# 8iPanelLED.net
KiCad netlist of a schematic drawn in EAGLE
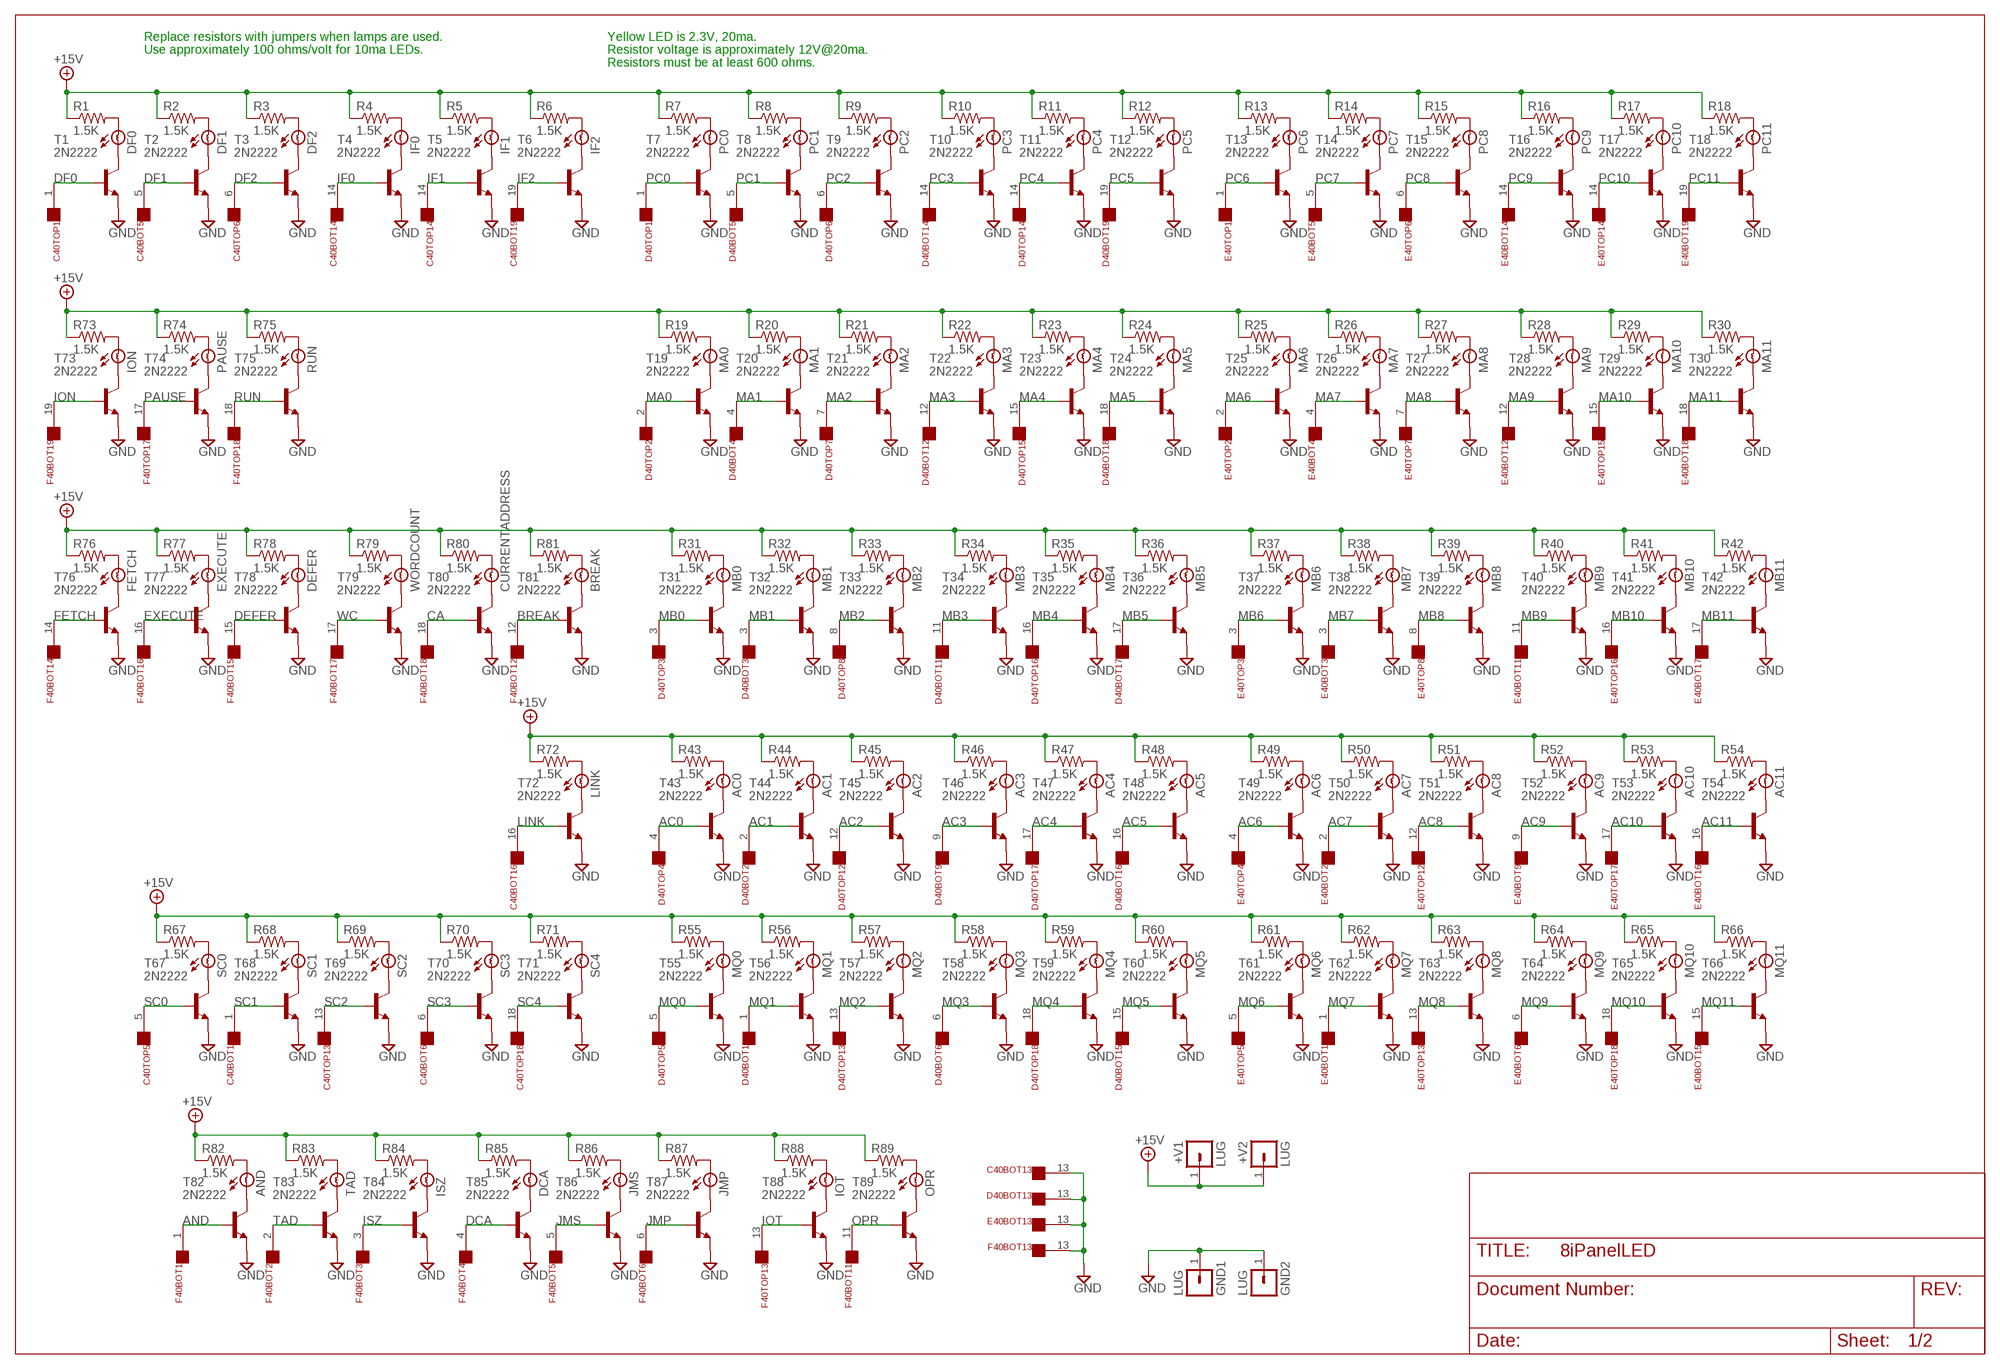
[diagram p0: schematic, sheet 1]
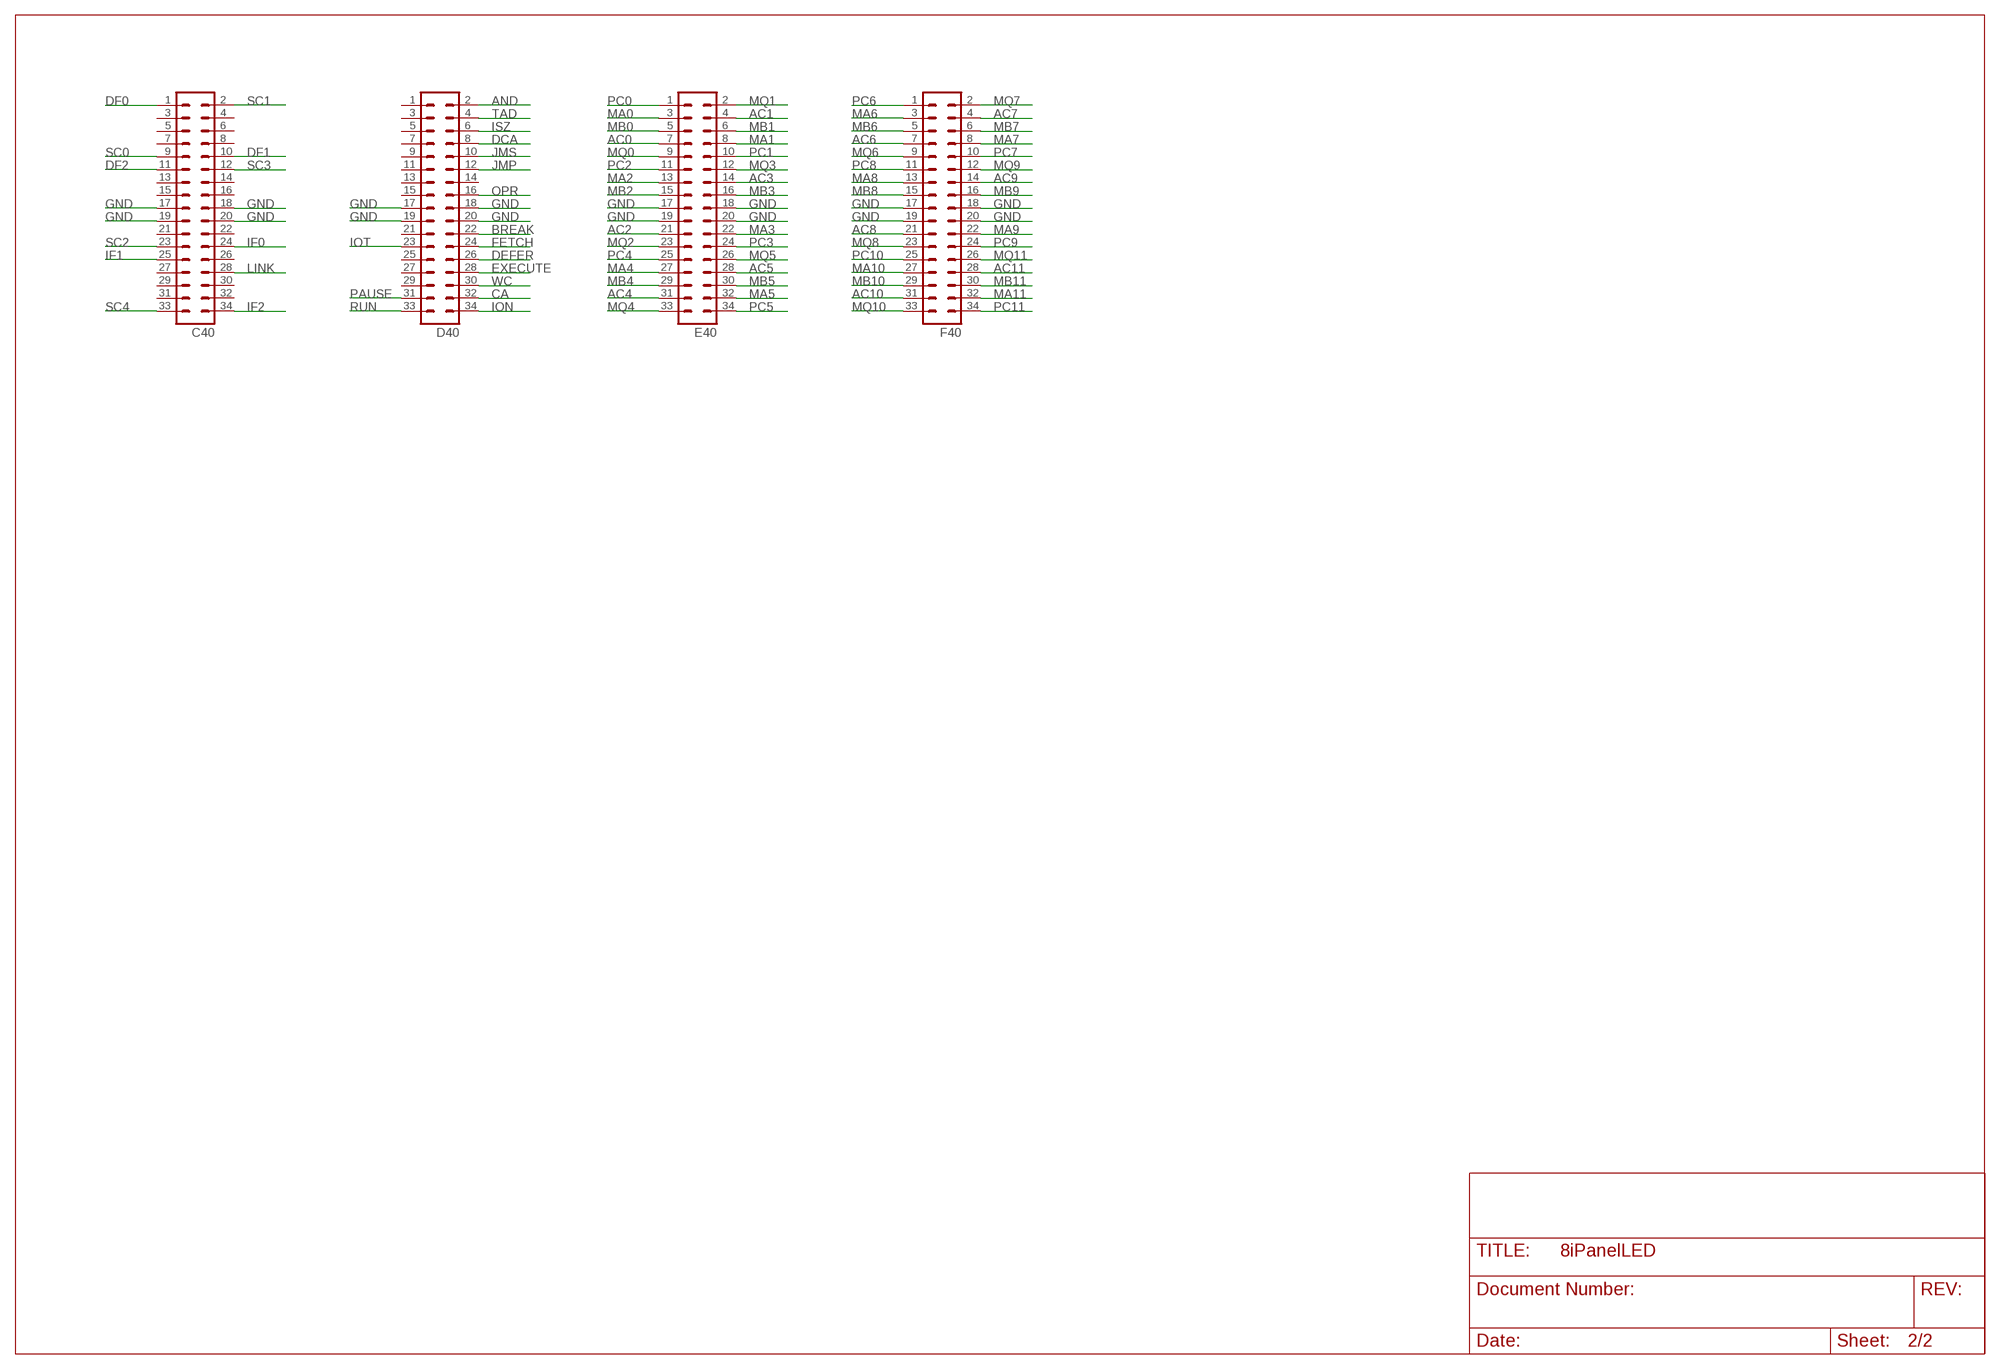
[diagram p1: schematic, sheet 2]

(export (version "E")
  (design (tool "Eeschema 10.0.6"))
  (components
    (comp (ref "+V1")
      (value "LUG")
      (footprint "eagle-import:SPADELUG")
      (libsource (lib "eagle-import") (part "LUG"))
    )
    (comp (ref "+V2")
      (value "LUG")
      (footprint "eagle-import:SPADELUG")
      (libsource (lib "eagle-import") (part "LUG"))
    )
    (comp (ref "AC0")
      (value "BULB")
      (footprint "eagle-import:BULB")
      (libsource (lib "eagle-import") (part "BULB"))
    )
    (comp (ref "AC1")
      (value "BULB")
      (footprint "eagle-import:BULB")
      (libsource (lib "eagle-import") (part "BULB"))
    )
    (comp (ref "AC2")
      (value "BULB")
      (footprint "eagle-import:BULB")
      (libsource (lib "eagle-import") (part "BULB"))
    )
    (comp (ref "AC3")
      (value "BULB")
      (footprint "eagle-import:BULB")
      (libsource (lib "eagle-import") (part "BULB"))
    )
    (comp (ref "AC4")
      (value "BULB")
      (footprint "eagle-import:BULB")
      (libsource (lib "eagle-import") (part "BULB"))
    )
    (comp (ref "AC5")
      (value "BULB")
      (footprint "eagle-import:BULB")
      (libsource (lib "eagle-import") (part "BULB"))
    )
    (comp (ref "AC6")
      (value "BULB")
      (footprint "eagle-import:BULB")
      (libsource (lib "eagle-import") (part "BULB"))
    )
    (comp (ref "AC7")
      (value "BULB")
      (footprint "eagle-import:BULB")
      (libsource (lib "eagle-import") (part "BULB"))
    )
    (comp (ref "AC8")
      (value "BULB")
      (footprint "eagle-import:BULB")
      (libsource (lib "eagle-import") (part "BULB"))
    )
    (comp (ref "AC9")
      (value "BULB")
      (footprint "eagle-import:BULB")
      (libsource (lib "eagle-import") (part "BULB"))
    )
    (comp (ref "AC10")
      (value "BULB")
      (footprint "eagle-import:BULB")
      (libsource (lib "eagle-import") (part "BULB"))
    )
    (comp (ref "AC11")
      (value "BULB")
      (footprint "eagle-import:BULB")
      (libsource (lib "eagle-import") (part "BULB"))
    )
    (comp (ref "AND")
      (value "BULB")
      (footprint "eagle-import:BULB")
      (libsource (lib "eagle-import") (part "BULB"))
    )
    (comp (ref "BREAK")
      (value "BULB")
      (footprint "eagle-import:BULB")
      (libsource (lib "eagle-import") (part "BULB"))
    )
    (comp (ref "C40BOT")
      (value "FLEX19")
      (footprint "eagle-import:FLEX19")
      (libsource (lib "eagle-import") (part "FLEX19"))
    )
    (comp (ref "C40TOP")
      (value "FLEX19")
      (footprint "eagle-import:FLEX19")
      (libsource (lib "eagle-import") (part "FLEX19"))
    )
    (comp (ref "CURRENTADDRESS")
      (value "BULB")
      (footprint "eagle-import:BULB")
      (libsource (lib "eagle-import") (part "BULB"))
    )
    (comp (ref "D40BOT")
      (value "FLEX19")
      (footprint "eagle-import:FLEX19")
      (libsource (lib "eagle-import") (part "FLEX19"))
    )
    (comp (ref "D40TOP")
      (value "FLEX19")
      (footprint "eagle-import:FLEX19")
      (libsource (lib "eagle-import") (part "FLEX19"))
    )
    (comp (ref "DCA")
      (value "BULB")
      (footprint "eagle-import:BULB")
      (libsource (lib "eagle-import") (part "BULB"))
    )
    (comp (ref "DEFER")
      (value "BULB")
      (footprint "eagle-import:BULB")
      (libsource (lib "eagle-import") (part "BULB"))
    )
    (comp (ref "DF0")
      (value "BULB")
      (footprint "eagle-import:BULB")
      (libsource (lib "eagle-import") (part "BULB"))
    )
    (comp (ref "DF1")
      (value "BULB")
      (footprint "eagle-import:BULB")
      (libsource (lib "eagle-import") (part "BULB"))
    )
    (comp (ref "DF2")
      (value "BULB")
      (footprint "eagle-import:BULB")
      (libsource (lib "eagle-import") (part "BULB"))
    )
    (comp (ref "E40BOT")
      (value "FLEX19")
      (footprint "eagle-import:FLEX19")
      (libsource (lib "eagle-import") (part "FLEX19"))
    )
    (comp (ref "E40TOP")
      (value "FLEX19")
      (footprint "eagle-import:FLEX19")
      (libsource (lib "eagle-import") (part "FLEX19"))
    )
    (comp (ref "EXECUTE")
      (value "BULB")
      (footprint "eagle-import:BULB")
      (libsource (lib "eagle-import") (part "BULB"))
    )
    (comp (ref "F40BOT")
      (value "FLEX19")
      (footprint "eagle-import:FLEX19")
      (libsource (lib "eagle-import") (part "FLEX19"))
    )
    (comp (ref "F40TOP")
      (value "FLEX19")
      (footprint "eagle-import:FLEX19")
      (libsource (lib "eagle-import") (part "FLEX19"))
    )
    (comp (ref "FETCH")
      (value "BULB")
      (footprint "eagle-import:BULB")
      (libsource (lib "eagle-import") (part "BULB"))
    )
    (comp (ref "GND1")
      (value "LUG")
      (footprint "eagle-import:SPADELUG")
      (libsource (lib "eagle-import") (part "LUG"))
    )
    (comp (ref "GND2")
      (value "LUG")
      (footprint "eagle-import:SPADELUG")
      (libsource (lib "eagle-import") (part "LUG"))
    )
    (comp (ref "IF0")
      (value "BULB")
      (footprint "eagle-import:BULB")
      (libsource (lib "eagle-import") (part "BULB"))
    )
    (comp (ref "IF1")
      (value "BULB")
      (footprint "eagle-import:BULB")
      (libsource (lib "eagle-import") (part "BULB"))
    )
    (comp (ref "IF2")
      (value "BULB")
      (footprint "eagle-import:BULB")
      (libsource (lib "eagle-import") (part "BULB"))
    )
    (comp (ref "ION")
      (value "BULB")
      (footprint "eagle-import:BULB")
      (libsource (lib "eagle-import") (part "BULB"))
    )
    (comp (ref "IOT")
      (value "BULB")
      (footprint "eagle-import:BULB")
      (libsource (lib "eagle-import") (part "BULB"))
    )
    (comp (ref "ISZ")
      (value "BULB")
      (footprint "eagle-import:BULB")
      (libsource (lib "eagle-import") (part "BULB"))
    )
    (comp (ref "JMP")
      (value "BULB")
      (footprint "eagle-import:BULB")
      (libsource (lib "eagle-import") (part "BULB"))
    )
    (comp (ref "JMS")
      (value "BULB")
      (footprint "eagle-import:BULB")
      (libsource (lib "eagle-import") (part "BULB"))
    )
    (comp (ref "LINK")
      (value "BULB")
      (footprint "eagle-import:BULB")
      (libsource (lib "eagle-import") (part "BULB"))
    )
    (comp (ref "MA0")
      (value "BULB")
      (footprint "eagle-import:BULB")
      (libsource (lib "eagle-import") (part "BULB"))
    )
    (comp (ref "MA1")
      (value "BULB")
      (footprint "eagle-import:BULB")
      (libsource (lib "eagle-import") (part "BULB"))
    )
    (comp (ref "MA2")
      (value "BULB")
      (footprint "eagle-import:BULB")
      (libsource (lib "eagle-import") (part "BULB"))
    )
    (comp (ref "MA3")
      (value "BULB")
      (footprint "eagle-import:BULB")
      (libsource (lib "eagle-import") (part "BULB"))
    )
    (comp (ref "MA4")
      (value "BULB")
      (footprint "eagle-import:BULB")
      (libsource (lib "eagle-import") (part "BULB"))
    )
    (comp (ref "MA5")
      (value "BULB")
      (footprint "eagle-import:BULB")
      (libsource (lib "eagle-import") (part "BULB"))
    )
    (comp (ref "MA6")
      (value "BULB")
      (footprint "eagle-import:BULB")
      (libsource (lib "eagle-import") (part "BULB"))
    )
    (comp (ref "MA7")
      (value "BULB")
      (footprint "eagle-import:BULB")
      (libsource (lib "eagle-import") (part "BULB"))
    )
    (comp (ref "MA8")
      (value "BULB")
      (footprint "eagle-import:BULB")
      (libsource (lib "eagle-import") (part "BULB"))
    )
    (comp (ref "MA9")
      (value "BULB")
      (footprint "eagle-import:BULB")
      (libsource (lib "eagle-import") (part "BULB"))
    )
    (comp (ref "MA10")
      (value "BULB")
      (footprint "eagle-import:BULB")
      (libsource (lib "eagle-import") (part "BULB"))
    )
    (comp (ref "MA11")
      (value "BULB")
      (footprint "eagle-import:BULB")
      (libsource (lib "eagle-import") (part "BULB"))
    )
    (comp (ref "MB0")
      (value "BULB")
      (footprint "eagle-import:BULB")
      (libsource (lib "eagle-import") (part "BULB"))
    )
    (comp (ref "MB1")
      (value "BULB")
      (footprint "eagle-import:BULB")
      (libsource (lib "eagle-import") (part "BULB"))
    )
    (comp (ref "MB2")
      (value "BULB")
      (footprint "eagle-import:BULB")
      (libsource (lib "eagle-import") (part "BULB"))
    )
    (comp (ref "MB3")
      (value "BULB")
      (footprint "eagle-import:BULB")
      (libsource (lib "eagle-import") (part "BULB"))
    )
    (comp (ref "MB4")
      (value "BULB")
      (footprint "eagle-import:BULB")
      (libsource (lib "eagle-import") (part "BULB"))
    )
    (comp (ref "MB5")
      (value "BULB")
      (footprint "eagle-import:BULB")
      (libsource (lib "eagle-import") (part "BULB"))
    )
    (comp (ref "MB6")
      (value "BULB")
      (footprint "eagle-import:BULB")
      (libsource (lib "eagle-import") (part "BULB"))
    )
    (comp (ref "MB7")
      (value "BULB")
      (footprint "eagle-import:BULB")
      (libsource (lib "eagle-import") (part "BULB"))
    )
    (comp (ref "MB8")
      (value "BULB")
      (footprint "eagle-import:BULB")
      (libsource (lib "eagle-import") (part "BULB"))
    )
    (comp (ref "MB9")
      (value "BULB")
      (footprint "eagle-import:BULB")
      (libsource (lib "eagle-import") (part "BULB"))
    )
    (comp (ref "MB10")
      (value "BULB")
      (footprint "eagle-import:BULB")
      (libsource (lib "eagle-import") (part "BULB"))
    )
    (comp (ref "MB11")
      (value "BULB")
      (footprint "eagle-import:BULB")
      (libsource (lib "eagle-import") (part "BULB"))
    )
    (comp (ref "MQ0")
      (value "BULB")
      (footprint "eagle-import:BULB")
      (libsource (lib "eagle-import") (part "BULB"))
    )
    (comp (ref "MQ1")
      (value "BULB")
      (footprint "eagle-import:BULB")
      (libsource (lib "eagle-import") (part "BULB"))
    )
    (comp (ref "MQ2")
      (value "BULB")
      (footprint "eagle-import:BULB")
      (libsource (lib "eagle-import") (part "BULB"))
    )
    (comp (ref "MQ3")
      (value "BULB")
      (footprint "eagle-import:BULB")
      (libsource (lib "eagle-import") (part "BULB"))
    )
    (comp (ref "MQ4")
      (value "BULB")
      (footprint "eagle-import:BULB")
      (libsource (lib "eagle-import") (part "BULB"))
    )
    (comp (ref "MQ5")
      (value "BULB")
      (footprint "eagle-import:BULB")
      (libsource (lib "eagle-import") (part "BULB"))
    )
    (comp (ref "MQ6")
      (value "BULB")
      (footprint "eagle-import:BULB")
      (libsource (lib "eagle-import") (part "BULB"))
    )
    (comp (ref "MQ7")
      (value "BULB")
      (footprint "eagle-import:BULB")
      (libsource (lib "eagle-import") (part "BULB"))
    )
    (comp (ref "MQ8")
      (value "BULB")
      (footprint "eagle-import:BULB")
      (libsource (lib "eagle-import") (part "BULB"))
    )
    (comp (ref "MQ9")
      (value "BULB")
      (footprint "eagle-import:BULB")
      (libsource (lib "eagle-import") (part "BULB"))
    )
    (comp (ref "MQ10")
      (value "BULB")
      (footprint "eagle-import:BULB")
      (libsource (lib "eagle-import") (part "BULB"))
    )
    (comp (ref "MQ11")
      (value "BULB")
      (footprint "eagle-import:BULB")
      (libsource (lib "eagle-import") (part "BULB"))
    )
    (comp (ref "OPR")
      (value "BULB")
      (footprint "eagle-import:BULB")
      (libsource (lib "eagle-import") (part "BULB"))
    )
    (comp (ref "PAUSE")
      (value "BULB")
      (footprint "eagle-import:BULB")
      (libsource (lib "eagle-import") (part "BULB"))
    )
    (comp (ref "PC0")
      (value "BULB")
      (footprint "eagle-import:BULB")
      (libsource (lib "eagle-import") (part "BULB"))
    )
    (comp (ref "PC1")
      (value "BULB")
      (footprint "eagle-import:BULB")
      (libsource (lib "eagle-import") (part "BULB"))
    )
    (comp (ref "PC2")
      (value "BULB")
      (footprint "eagle-import:BULB")
      (libsource (lib "eagle-import") (part "BULB"))
    )
    (comp (ref "PC3")
      (value "BULB")
      (footprint "eagle-import:BULB")
      (libsource (lib "eagle-import") (part "BULB"))
    )
    (comp (ref "PC4")
      (value "BULB")
      (footprint "eagle-import:BULB")
      (libsource (lib "eagle-import") (part "BULB"))
    )
    (comp (ref "PC5")
      (value "BULB")
      (footprint "eagle-import:BULB")
      (libsource (lib "eagle-import") (part "BULB"))
    )
    (comp (ref "PC6")
      (value "BULB")
      (footprint "eagle-import:BULB")
      (libsource (lib "eagle-import") (part "BULB"))
    )
    (comp (ref "PC7")
      (value "BULB")
      (footprint "eagle-import:BULB")
      (libsource (lib "eagle-import") (part "BULB"))
    )
    (comp (ref "PC8")
      (value "BULB")
      (footprint "eagle-import:BULB")
      (libsource (lib "eagle-import") (part "BULB"))
    )
    (comp (ref "PC9")
      (value "BULB")
      (footprint "eagle-import:BULB")
      (libsource (lib "eagle-import") (part "BULB"))
    )
    (comp (ref "PC10")
      (value "BULB")
      (footprint "eagle-import:BULB")
      (libsource (lib "eagle-import") (part "BULB"))
    )
    (comp (ref "PC11")
      (value "BULB")
      (footprint "eagle-import:BULB")
      (libsource (lib "eagle-import") (part "BULB"))
    )
    (comp (ref "R1")
      (value "1.5K")
      (footprint "eagle-import:0207_10")
      (libsource (lib "eagle-import") (part "R-US_0207/10"))
    )
    (comp (ref "R2")
      (value "1.5K")
      (footprint "eagle-import:0207_10")
      (libsource (lib "eagle-import") (part "R-US_0207/10"))
    )
    (comp (ref "R3")
      (value "1.5K")
      (footprint "eagle-import:0207_10")
      (libsource (lib "eagle-import") (part "R-US_0207/10"))
    )
    (comp (ref "R4")
      (value "1.5K")
      (footprint "eagle-import:0207_10")
      (libsource (lib "eagle-import") (part "R-US_0207/10"))
    )
    (comp (ref "R5")
      (value "1.5K")
      (footprint "eagle-import:0207_10")
      (libsource (lib "eagle-import") (part "R-US_0207/10"))
    )
    (comp (ref "R6")
      (value "1.5K")
      (footprint "eagle-import:0207_10")
      (libsource (lib "eagle-import") (part "R-US_0207/10"))
    )
    (comp (ref "R7")
      (value "1.5K")
      (footprint "eagle-import:0207_10")
      (libsource (lib "eagle-import") (part "R-US_0207/10"))
    )
    (comp (ref "R8")
      (value "1.5K")
      (footprint "eagle-import:0207_10")
      (libsource (lib "eagle-import") (part "R-US_0207/10"))
    )
    (comp (ref "R9")
      (value "1.5K")
      (footprint "eagle-import:0207_10")
      (libsource (lib "eagle-import") (part "R-US_0207/10"))
    )
    (comp (ref "R10")
      (value "1.5K")
      (footprint "eagle-import:0207_10")
      (libsource (lib "eagle-import") (part "R-US_0207/10"))
    )
    (comp (ref "R11")
      (value "1.5K")
      (footprint "eagle-import:0207_10")
      (libsource (lib "eagle-import") (part "R-US_0207/10"))
    )
    (comp (ref "R12")
      (value "1.5K")
      (footprint "eagle-import:0207_10")
      (libsource (lib "eagle-import") (part "R-US_0207/10"))
    )
    (comp (ref "R13")
      (value "1.5K")
      (footprint "eagle-import:0207_10")
      (libsource (lib "eagle-import") (part "R-US_0207/10"))
    )
    (comp (ref "R14")
      (value "1.5K")
      (footprint "eagle-import:0207_10")
      (libsource (lib "eagle-import") (part "R-US_0207/10"))
    )
    (comp (ref "R15")
      (value "1.5K")
      (footprint "eagle-import:0207_10")
      (libsource (lib "eagle-import") (part "R-US_0207/10"))
    )
    (comp (ref "R16")
      (value "1.5K")
      (footprint "eagle-import:0207_10")
      (libsource (lib "eagle-import") (part "R-US_0207/10"))
    )
    (comp (ref "R17")
      (value "1.5K")
      (footprint "eagle-import:0207_10")
      (libsource (lib "eagle-import") (part "R-US_0207/10"))
    )
    (comp (ref "R18")
      (value "1.5K")
      (footprint "eagle-import:0207_10")
      (libsource (lib "eagle-import") (part "R-US_0207/10"))
    )
    (comp (ref "R19")
      (value "1.5K")
      (footprint "eagle-import:0207_10")
      (libsource (lib "eagle-import") (part "R-US_0207/10"))
    )
    (comp (ref "R20")
      (value "1.5K")
      (footprint "eagle-import:0207_10")
      (libsource (lib "eagle-import") (part "R-US_0207/10"))
    )
    (comp (ref "R21")
      (value "1.5K")
      (footprint "eagle-import:0207_10")
      (libsource (lib "eagle-import") (part "R-US_0207/10"))
    )
    (comp (ref "R22")
      (value "1.5K")
      (footprint "eagle-import:0207_10")
      (libsource (lib "eagle-import") (part "R-US_0207/10"))
    )
    (comp (ref "R23")
      (value "1.5K")
      (footprint "eagle-import:0207_10")
      (libsource (lib "eagle-import") (part "R-US_0207/10"))
    )
    (comp (ref "R24")
      (value "1.5K")
      (footprint "eagle-import:0207_10")
      (libsource (lib "eagle-import") (part "R-US_0207/10"))
    )
    (comp (ref "R25")
      (value "1.5K")
      (footprint "eagle-import:0207_10")
      (libsource (lib "eagle-import") (part "R-US_0207/10"))
    )
    (comp (ref "R26")
      (value "1.5K")
      (footprint "eagle-import:0207_10")
      (libsource (lib "eagle-import") (part "R-US_0207/10"))
    )
    (comp (ref "R27")
      (value "1.5K")
      (footprint "eagle-import:0207_10")
      (libsource (lib "eagle-import") (part "R-US_0207/10"))
    )
    (comp (ref "R28")
      (value "1.5K")
      (footprint "eagle-import:0207_10")
      (libsource (lib "eagle-import") (part "R-US_0207/10"))
    )
    (comp (ref "R29")
      (value "1.5K")
      (footprint "eagle-import:0207_10")
      (libsource (lib "eagle-import") (part "R-US_0207/10"))
    )
    (comp (ref "R30")
      (value "1.5K")
      (footprint "eagle-import:0207_10")
      (libsource (lib "eagle-import") (part "R-US_0207/10"))
    )
    (comp (ref "R31")
      (value "1.5K")
      (footprint "eagle-import:0207_10")
      (libsource (lib "eagle-import") (part "R-US_0207/10"))
    )
    (comp (ref "R32")
      (value "1.5K")
      (footprint "eagle-import:0207_10")
      (libsource (lib "eagle-import") (part "R-US_0207/10"))
    )
    (comp (ref "R33")
      (value "1.5K")
      (footprint "eagle-import:0207_10")
      (libsource (lib "eagle-import") (part "R-US_0207/10"))
    )
    (comp (ref "R34")
      (value "1.5K")
      (footprint "eagle-import:0207_10")
      (libsource (lib "eagle-import") (part "R-US_0207/10"))
    )
    (comp (ref "R35")
      (value "1.5K")
      (footprint "eagle-import:0207_10")
      (libsource (lib "eagle-import") (part "R-US_0207/10"))
    )
    (comp (ref "R36")
      (value "1.5K")
      (footprint "eagle-import:0207_10")
      (libsource (lib "eagle-import") (part "R-US_0207/10"))
    )
    (comp (ref "R37")
      (value "1.5K")
      (footprint "eagle-import:0207_10")
      (libsource (lib "eagle-import") (part "R-US_0207/10"))
    )
    (comp (ref "R38")
      (value "1.5K")
      (footprint "eagle-import:0207_10")
      (libsource (lib "eagle-import") (part "R-US_0207/10"))
    )
    (comp (ref "R39")
      (value "1.5K")
      (footprint "eagle-import:0207_10")
      (libsource (lib "eagle-import") (part "R-US_0207/10"))
    )
    (comp (ref "R40")
      (value "1.5K")
      (footprint "eagle-import:0207_10")
      (libsource (lib "eagle-import") (part "R-US_0207/10"))
    )
    (comp (ref "R41")
      (value "1.5K")
      (footprint "eagle-import:0207_10")
      (libsource (lib "eagle-import") (part "R-US_0207/10"))
    )
    (comp (ref "R42")
      (value "1.5K")
      (footprint "eagle-import:0207_10")
      (libsource (lib "eagle-import") (part "R-US_0207/10"))
    )
    (comp (ref "R43")
      (value "1.5K")
      (footprint "eagle-import:0207_10")
      (libsource (lib "eagle-import") (part "R-US_0207/10"))
    )
    (comp (ref "R44")
      (value "1.5K")
      (footprint "eagle-import:0207_10")
      (libsource (lib "eagle-import") (part "R-US_0207/10"))
    )
    (comp (ref "R45")
      (value "1.5K")
      (footprint "eagle-import:0207_10")
      (libsource (lib "eagle-import") (part "R-US_0207/10"))
    )
    (comp (ref "R46")
      (value "1.5K")
      (footprint "eagle-import:0207_10")
      (libsource (lib "eagle-import") (part "R-US_0207/10"))
    )
    (comp (ref "R47")
      (value "1.5K")
      (footprint "eagle-import:0207_10")
      (libsource (lib "eagle-import") (part "R-US_0207/10"))
    )
    (comp (ref "R48")
      (value "1.5K")
      (footprint "eagle-import:0207_10")
      (libsource (lib "eagle-import") (part "R-US_0207/10"))
    )
    (comp (ref "R49")
      (value "1.5K")
      (footprint "eagle-import:0207_10")
      (libsource (lib "eagle-import") (part "R-US_0207/10"))
    )
    (comp (ref "R50")
      (value "1.5K")
      (footprint "eagle-import:0207_10")
      (libsource (lib "eagle-import") (part "R-US_0207/10"))
    )
    (comp (ref "R51")
      (value "1.5K")
      (footprint "eagle-import:0207_10")
      (libsource (lib "eagle-import") (part "R-US_0207/10"))
    )
    (comp (ref "R52")
      (value "1.5K")
      (footprint "eagle-import:0207_10")
      (libsource (lib "eagle-import") (part "R-US_0207/10"))
    )
    (comp (ref "R53")
      (value "1.5K")
      (footprint "eagle-import:0207_10")
      (libsource (lib "eagle-import") (part "R-US_0207/10"))
    )
    (comp (ref "R54")
      (value "1.5K")
      (footprint "eagle-import:0207_10")
      (libsource (lib "eagle-import") (part "R-US_0207/10"))
    )
    (comp (ref "R55")
      (value "1.5K")
      (footprint "eagle-import:0207_10")
      (libsource (lib "eagle-import") (part "R-US_0207/10"))
    )
    (comp (ref "R56")
      (value "1.5K")
      (footprint "eagle-import:0207_10")
      (libsource (lib "eagle-import") (part "R-US_0207/10"))
    )
    (comp (ref "R57")
      (value "1.5K")
      (footprint "eagle-import:0207_10")
      (libsource (lib "eagle-import") (part "R-US_0207/10"))
    )
    (comp (ref "R58")
      (value "1.5K")
      (footprint "eagle-import:0207_10")
      (libsource (lib "eagle-import") (part "R-US_0207/10"))
    )
    (comp (ref "R59")
      (value "1.5K")
      (footprint "eagle-import:0207_10")
      (libsource (lib "eagle-import") (part "R-US_0207/10"))
    )
    (comp (ref "R60")
      (value "1.5K")
      (footprint "eagle-import:0207_10")
      (libsource (lib "eagle-import") (part "R-US_0207/10"))
    )
    (comp (ref "R61")
      (value "1.5K")
      (footprint "eagle-import:0207_10")
      (libsource (lib "eagle-import") (part "R-US_0207/10"))
    )
    (comp (ref "R62")
      (value "1.5K")
      (footprint "eagle-import:0207_10")
      (libsource (lib "eagle-import") (part "R-US_0207/10"))
    )
    (comp (ref "R63")
      (value "1.5K")
      (footprint "eagle-import:0207_10")
      (libsource (lib "eagle-import") (part "R-US_0207/10"))
    )
    (comp (ref "R64")
      (value "1.5K")
      (footprint "eagle-import:0207_10")
      (libsource (lib "eagle-import") (part "R-US_0207/10"))
    )
    (comp (ref "R65")
      (value "1.5K")
      (footprint "eagle-import:0207_10")
      (libsource (lib "eagle-import") (part "R-US_0207/10"))
    )
    (comp (ref "R66")
      (value "1.5K")
      (footprint "eagle-import:0207_10")
      (libsource (lib "eagle-import") (part "R-US_0207/10"))
    )
    (comp (ref "R67")
      (value "1.5K")
      (footprint "eagle-import:0207_10")
      (libsource (lib "eagle-import") (part "R-US_0207/10"))
    )
    (comp (ref "R68")
      (value "1.5K")
      (footprint "eagle-import:0207_10")
      (libsource (lib "eagle-import") (part "R-US_0207/10"))
    )
    (comp (ref "R69")
      (value "1.5K")
      (footprint "eagle-import:0207_10")
      (libsource (lib "eagle-import") (part "R-US_0207/10"))
    )
    (comp (ref "R70")
      (value "1.5K")
      (footprint "eagle-import:0207_10")
      (libsource (lib "eagle-import") (part "R-US_0207/10"))
    )
    (comp (ref "R71")
      (value "1.5K")
      (footprint "eagle-import:0207_10")
      (libsource (lib "eagle-import") (part "R-US_0207/10"))
    )
    (comp (ref "R72")
      (value "1.5K")
      (footprint "eagle-import:0207_10")
      (libsource (lib "eagle-import") (part "R-US_0207/10"))
    )
    (comp (ref "R73")
      (value "1.5K")
      (footprint "eagle-import:0207_10")
      (libsource (lib "eagle-import") (part "R-US_0207/10"))
    )
    (comp (ref "R74")
      (value "1.5K")
      (footprint "eagle-import:0207_10")
      (libsource (lib "eagle-import") (part "R-US_0207/10"))
    )
    (comp (ref "R75")
      (value "1.5K")
      (footprint "eagle-import:0207_10")
      (libsource (lib "eagle-import") (part "R-US_0207/10"))
    )
    (comp (ref "R76")
      (value "1.5K")
      (footprint "eagle-import:0207_10")
      (libsource (lib "eagle-import") (part "R-US_0207/10"))
    )
    (comp (ref "R77")
      (value "1.5K")
      (footprint "eagle-import:0207_10")
      (libsource (lib "eagle-import") (part "R-US_0207/10"))
    )
    (comp (ref "R78")
      (value "1.5K")
      (footprint "eagle-import:0207_10")
      (libsource (lib "eagle-import") (part "R-US_0207/10"))
    )
    (comp (ref "R79")
      (value "1.5K")
      (footprint "eagle-import:0207_10")
      (libsource (lib "eagle-import") (part "R-US_0207/10"))
    )
    (comp (ref "R80")
      (value "1.5K")
      (footprint "eagle-import:0207_10")
      (libsource (lib "eagle-import") (part "R-US_0207/10"))
    )
    (comp (ref "R81")
      (value "1.5K")
      (footprint "eagle-import:0207_10")
      (libsource (lib "eagle-import") (part "R-US_0207/10"))
    )
    (comp (ref "R82")
      (value "1.5K")
      (footprint "eagle-import:0207_10")
      (libsource (lib "eagle-import") (part "R-US_0207/10"))
    )
    (comp (ref "R83")
      (value "1.5K")
      (footprint "eagle-import:0207_10")
      (libsource (lib "eagle-import") (part "R-US_0207/10"))
    )
    (comp (ref "R84")
      (value "1.5K")
      (footprint "eagle-import:0207_10")
      (libsource (lib "eagle-import") (part "R-US_0207/10"))
    )
    (comp (ref "R85")
      (value "1.5K")
      (footprint "eagle-import:0207_10")
      (libsource (lib "eagle-import") (part "R-US_0207/10"))
    )
    (comp (ref "R86")
      (value "1.5K")
      (footprint "eagle-import:0207_10")
      (libsource (lib "eagle-import") (part "R-US_0207/10"))
    )
    (comp (ref "R87")
      (value "1.5K")
      (footprint "eagle-import:0207_10")
      (libsource (lib "eagle-import") (part "R-US_0207/10"))
    )
    (comp (ref "R88")
      (value "1.5K")
      (footprint "eagle-import:0207_10")
      (libsource (lib "eagle-import") (part "R-US_0207/10"))
    )
    (comp (ref "R89")
      (value "1.5K")
      (footprint "eagle-import:0207_10")
      (libsource (lib "eagle-import") (part "R-US_0207/10"))
    )
    (comp (ref "RUN")
      (value "BULB")
      (footprint "eagle-import:BULB")
      (libsource (lib "eagle-import") (part "BULB"))
    )
    (comp (ref "SC0")
      (value "BULB")
      (footprint "eagle-import:BULB")
      (libsource (lib "eagle-import") (part "BULB"))
    )
    (comp (ref "SC1")
      (value "BULB")
      (footprint "eagle-import:BULB")
      (libsource (lib "eagle-import") (part "BULB"))
    )
    (comp (ref "SC2")
      (value "BULB")
      (footprint "eagle-import:BULB")
      (libsource (lib "eagle-import") (part "BULB"))
    )
    (comp (ref "SC3")
      (value "BULB")
      (footprint "eagle-import:BULB")
      (libsource (lib "eagle-import") (part "BULB"))
    )
    (comp (ref "SC4")
      (value "BULB")
      (footprint "eagle-import:BULB")
      (libsource (lib "eagle-import") (part "BULB"))
    )
    (comp (ref "T1")
      (value "2N2222")
      (footprint "eagle-import:TO92")
      (libsource (lib "eagle-import") (part "-NPN-TO92"))
    )
    (comp (ref "T2")
      (value "2N2222")
      (footprint "eagle-import:TO92")
      (libsource (lib "eagle-import") (part "-NPN-TO92"))
    )
    (comp (ref "T3")
      (value "2N2222")
      (footprint "eagle-import:TO92")
      (libsource (lib "eagle-import") (part "-NPN-TO92"))
    )
    (comp (ref "T4")
      (value "2N2222")
      (footprint "eagle-import:TO92")
      (libsource (lib "eagle-import") (part "-NPN-TO92"))
    )
    (comp (ref "T5")
      (value "2N2222")
      (footprint "eagle-import:TO92")
      (libsource (lib "eagle-import") (part "-NPN-TO92"))
    )
    (comp (ref "T6")
      (value "2N2222")
      (footprint "eagle-import:TO92")
      (libsource (lib "eagle-import") (part "-NPN-TO92"))
    )
    (comp (ref "T7")
      (value "2N2222")
      (footprint "eagle-import:TO92")
      (libsource (lib "eagle-import") (part "-NPN-TO92"))
    )
    (comp (ref "T8")
      (value "2N2222")
      (footprint "eagle-import:TO92")
      (libsource (lib "eagle-import") (part "-NPN-TO92"))
    )
    (comp (ref "T9")
      (value "2N2222")
      (footprint "eagle-import:TO92")
      (libsource (lib "eagle-import") (part "-NPN-TO92"))
    )
    (comp (ref "T10")
      (value "2N2222")
      (footprint "eagle-import:TO92")
      (libsource (lib "eagle-import") (part "-NPN-TO92"))
    )
    (comp (ref "T11")
      (value "2N2222")
      (footprint "eagle-import:TO92")
      (libsource (lib "eagle-import") (part "-NPN-TO92"))
    )
    (comp (ref "T12")
      (value "2N2222")
      (footprint "eagle-import:TO92")
      (libsource (lib "eagle-import") (part "-NPN-TO92"))
    )
    (comp (ref "T13")
      (value "2N2222")
      (footprint "eagle-import:TO92")
      (libsource (lib "eagle-import") (part "-NPN-TO92"))
    )
    (comp (ref "T14")
      (value "2N2222")
      (footprint "eagle-import:TO92")
      (libsource (lib "eagle-import") (part "-NPN-TO92"))
    )
    (comp (ref "T15")
      (value "2N2222")
      (footprint "eagle-import:TO92")
      (libsource (lib "eagle-import") (part "-NPN-TO92"))
    )
    (comp (ref "T16")
      (value "2N2222")
      (footprint "eagle-import:TO92")
      (libsource (lib "eagle-import") (part "-NPN-TO92"))
    )
    (comp (ref "T17")
      (value "2N2222")
      (footprint "eagle-import:TO92")
      (libsource (lib "eagle-import") (part "-NPN-TO92"))
    )
    (comp (ref "T18")
      (value "2N2222")
      (footprint "eagle-import:TO92")
      (libsource (lib "eagle-import") (part "-NPN-TO92"))
    )
    (comp (ref "T19")
      (value "2N2222")
      (footprint "eagle-import:TO92")
      (libsource (lib "eagle-import") (part "-NPN-TO92"))
    )
    (comp (ref "T20")
      (value "2N2222")
      (footprint "eagle-import:TO92")
      (libsource (lib "eagle-import") (part "-NPN-TO92"))
    )
    (comp (ref "T21")
      (value "2N2222")
      (footprint "eagle-import:TO92")
      (libsource (lib "eagle-import") (part "-NPN-TO92"))
    )
    (comp (ref "T22")
      (value "2N2222")
      (footprint "eagle-import:TO92")
      (libsource (lib "eagle-import") (part "-NPN-TO92"))
    )
    (comp (ref "T23")
      (value "2N2222")
      (footprint "eagle-import:TO92")
      (libsource (lib "eagle-import") (part "-NPN-TO92"))
    )
    (comp (ref "T24")
      (value "2N2222")
      (footprint "eagle-import:TO92")
      (libsource (lib "eagle-import") (part "-NPN-TO92"))
    )
    (comp (ref "T25")
      (value "2N2222")
      (footprint "eagle-import:TO92")
      (libsource (lib "eagle-import") (part "-NPN-TO92"))
    )
    (comp (ref "T26")
      (value "2N2222")
      (footprint "eagle-import:TO92")
      (libsource (lib "eagle-import") (part "-NPN-TO92"))
    )
    (comp (ref "T27")
      (value "2N2222")
      (footprint "eagle-import:TO92")
      (libsource (lib "eagle-import") (part "-NPN-TO92"))
    )
    (comp (ref "T28")
      (value "2N2222")
      (footprint "eagle-import:TO92")
      (libsource (lib "eagle-import") (part "-NPN-TO92"))
    )
    (comp (ref "T29")
      (value "2N2222")
      (footprint "eagle-import:TO92")
      (libsource (lib "eagle-import") (part "-NPN-TO92"))
    )
    (comp (ref "T30")
      (value "2N2222")
      (footprint "eagle-import:TO92")
      (libsource (lib "eagle-import") (part "-NPN-TO92"))
    )
    (comp (ref "T31")
      (value "2N2222")
      (footprint "eagle-import:TO92")
      (libsource (lib "eagle-import") (part "-NPN-TO92"))
    )
    (comp (ref "T32")
      (value "2N2222")
      (footprint "eagle-import:TO92")
      (libsource (lib "eagle-import") (part "-NPN-TO92"))
    )
    (comp (ref "T33")
      (value "2N2222")
      (footprint "eagle-import:TO92")
      (libsource (lib "eagle-import") (part "-NPN-TO92"))
    )
    (comp (ref "T34")
      (value "2N2222")
      (footprint "eagle-import:TO92")
      (libsource (lib "eagle-import") (part "-NPN-TO92"))
    )
    (comp (ref "T35")
      (value "2N2222")
      (footprint "eagle-import:TO92")
      (libsource (lib "eagle-import") (part "-NPN-TO92"))
    )
    (comp (ref "T36")
      (value "2N2222")
      (footprint "eagle-import:TO92")
      (libsource (lib "eagle-import") (part "-NPN-TO92"))
    )
    (comp (ref "T37")
      (value "2N2222")
      (footprint "eagle-import:TO92")
      (libsource (lib "eagle-import") (part "-NPN-TO92"))
    )
    (comp (ref "T38")
      (value "2N2222")
      (footprint "eagle-import:TO92")
      (libsource (lib "eagle-import") (part "-NPN-TO92"))
    )
    (comp (ref "T39")
      (value "2N2222")
      (footprint "eagle-import:TO92")
      (libsource (lib "eagle-import") (part "-NPN-TO92"))
    )
    (comp (ref "T40")
      (value "2N2222")
      (footprint "eagle-import:TO92")
      (libsource (lib "eagle-import") (part "-NPN-TO92"))
    )
    (comp (ref "T41")
      (value "2N2222")
      (footprint "eagle-import:TO92")
      (libsource (lib "eagle-import") (part "-NPN-TO92"))
    )
    (comp (ref "T42")
      (value "2N2222")
      (footprint "eagle-import:TO92")
      (libsource (lib "eagle-import") (part "-NPN-TO92"))
    )
    (comp (ref "T43")
      (value "2N2222")
      (footprint "eagle-import:TO92")
      (libsource (lib "eagle-import") (part "-NPN-TO92"))
    )
    (comp (ref "T44")
      (value "2N2222")
      (footprint "eagle-import:TO92")
      (libsource (lib "eagle-import") (part "-NPN-TO92"))
    )
    (comp (ref "T45")
      (value "2N2222")
      (footprint "eagle-import:TO92")
      (libsource (lib "eagle-import") (part "-NPN-TO92"))
    )
    (comp (ref "T46")
      (value "2N2222")
      (footprint "eagle-import:TO92")
      (libsource (lib "eagle-import") (part "-NPN-TO92"))
    )
    (comp (ref "T47")
      (value "2N2222")
      (footprint "eagle-import:TO92")
      (libsource (lib "eagle-import") (part "-NPN-TO92"))
    )
    (comp (ref "T48")
      (value "2N2222")
      (footprint "eagle-import:TO92")
      (libsource (lib "eagle-import") (part "-NPN-TO92"))
    )
    (comp (ref "T49")
      (value "2N2222")
      (footprint "eagle-import:TO92")
      (libsource (lib "eagle-import") (part "-NPN-TO92"))
    )
    (comp (ref "T50")
      (value "2N2222")
      (footprint "eagle-import:TO92")
      (libsource (lib "eagle-import") (part "-NPN-TO92"))
    )
    (comp (ref "T51")
      (value "2N2222")
      (footprint "eagle-import:TO92")
      (libsource (lib "eagle-import") (part "-NPN-TO92"))
    )
    (comp (ref "T52")
      (value "2N2222")
      (footprint "eagle-import:TO92")
      (libsource (lib "eagle-import") (part "-NPN-TO92"))
    )
    (comp (ref "T53")
      (value "2N2222")
      (footprint "eagle-import:TO92")
      (libsource (lib "eagle-import") (part "-NPN-TO92"))
    )
    (comp (ref "T54")
      (value "2N2222")
      (footprint "eagle-import:TO92")
      (libsource (lib "eagle-import") (part "-NPN-TO92"))
    )
    (comp (ref "T55")
      (value "2N2222")
      (footprint "eagle-import:TO92")
      (libsource (lib "eagle-import") (part "-NPN-TO92"))
    )
    (comp (ref "T56")
      (value "2N2222")
      (footprint "eagle-import:TO92")
      (libsource (lib "eagle-import") (part "-NPN-TO92"))
    )
    (comp (ref "T57")
      (value "2N2222")
      (footprint "eagle-import:TO92")
      (libsource (lib "eagle-import") (part "-NPN-TO92"))
    )
    (comp (ref "T58")
      (value "2N2222")
      (footprint "eagle-import:TO92")
      (libsource (lib "eagle-import") (part "-NPN-TO92"))
    )
    (comp (ref "T59")
      (value "2N2222")
      (footprint "eagle-import:TO92")
      (libsource (lib "eagle-import") (part "-NPN-TO92"))
    )
    (comp (ref "T60")
      (value "2N2222")
      (footprint "eagle-import:TO92")
      (libsource (lib "eagle-import") (part "-NPN-TO92"))
    )
    (comp (ref "T61")
      (value "2N2222")
      (footprint "eagle-import:TO92")
      (libsource (lib "eagle-import") (part "-NPN-TO92"))
    )
    (comp (ref "T62")
      (value "2N2222")
      (footprint "eagle-import:TO92")
      (libsource (lib "eagle-import") (part "-NPN-TO92"))
    )
    (comp (ref "T63")
      (value "2N2222")
      (footprint "eagle-import:TO92")
      (libsource (lib "eagle-import") (part "-NPN-TO92"))
    )
    (comp (ref "T64")
      (value "2N2222")
      (footprint "eagle-import:TO92")
      (libsource (lib "eagle-import") (part "-NPN-TO92"))
    )
    (comp (ref "T65")
      (value "2N2222")
      (footprint "eagle-import:TO92")
      (libsource (lib "eagle-import") (part "-NPN-TO92"))
    )
    (comp (ref "T66")
      (value "2N2222")
      (footprint "eagle-import:TO92")
      (libsource (lib "eagle-import") (part "-NPN-TO92"))
    )
    (comp (ref "T67")
      (value "2N2222")
      (footprint "eagle-import:TO92")
      (libsource (lib "eagle-import") (part "-NPN-TO92"))
    )
    (comp (ref "T68")
      (value "2N2222")
      (footprint "eagle-import:TO92")
      (libsource (lib "eagle-import") (part "-NPN-TO92"))
    )
    (comp (ref "T69")
      (value "2N2222")
      (footprint "eagle-import:TO92")
      (libsource (lib "eagle-import") (part "-NPN-TO92"))
    )
    (comp (ref "T70")
      (value "2N2222")
      (footprint "eagle-import:TO92")
      (libsource (lib "eagle-import") (part "-NPN-TO92"))
    )
    (comp (ref "T71")
      (value "2N2222")
      (footprint "eagle-import:TO92")
      (libsource (lib "eagle-import") (part "-NPN-TO92"))
    )
    (comp (ref "T72")
      (value "2N2222")
      (footprint "eagle-import:TO92")
      (libsource (lib "eagle-import") (part "-NPN-TO92"))
    )
    (comp (ref "T73")
      (value "2N2222")
      (footprint "eagle-import:TO92")
      (libsource (lib "eagle-import") (part "-NPN-TO92"))
    )
    (comp (ref "T74")
      (value "2N2222")
      (footprint "eagle-import:TO92")
      (libsource (lib "eagle-import") (part "-NPN-TO92"))
    )
    (comp (ref "T75")
      (value "2N2222")
      (footprint "eagle-import:TO92")
      (libsource (lib "eagle-import") (part "-NPN-TO92"))
    )
    (comp (ref "T76")
      (value "2N2222")
      (footprint "eagle-import:TO92")
      (libsource (lib "eagle-import") (part "-NPN-TO92"))
    )
    (comp (ref "T77")
      (value "2N2222")
      (footprint "eagle-import:TO92")
      (libsource (lib "eagle-import") (part "-NPN-TO92"))
    )
    (comp (ref "T78")
      (value "2N2222")
      (footprint "eagle-import:TO92")
      (libsource (lib "eagle-import") (part "-NPN-TO92"))
    )
    (comp (ref "T79")
      (value "2N2222")
      (footprint "eagle-import:TO92")
      (libsource (lib "eagle-import") (part "-NPN-TO92"))
    )
    (comp (ref "T80")
      (value "2N2222")
      (footprint "eagle-import:TO92")
      (libsource (lib "eagle-import") (part "-NPN-TO92"))
    )
    (comp (ref "T81")
      (value "2N2222")
      (footprint "eagle-import:TO92")
      (libsource (lib "eagle-import") (part "-NPN-TO92"))
    )
    (comp (ref "T82")
      (value "2N2222")
      (footprint "eagle-import:TO92")
      (libsource (lib "eagle-import") (part "-NPN-TO92"))
    )
    (comp (ref "T83")
      (value "2N2222")
      (footprint "eagle-import:TO92")
      (libsource (lib "eagle-import") (part "-NPN-TO92"))
    )
    (comp (ref "T84")
      (value "2N2222")
      (footprint "eagle-import:TO92")
      (libsource (lib "eagle-import") (part "-NPN-TO92"))
    )
    (comp (ref "T85")
      (value "2N2222")
      (footprint "eagle-import:TO92")
      (libsource (lib "eagle-import") (part "-NPN-TO92"))
    )
    (comp (ref "T86")
      (value "2N2222")
      (footprint "eagle-import:TO92")
      (libsource (lib "eagle-import") (part "-NPN-TO92"))
    )
    (comp (ref "T87")
      (value "2N2222")
      (footprint "eagle-import:TO92")
      (libsource (lib "eagle-import") (part "-NPN-TO92"))
    )
    (comp (ref "T88")
      (value "2N2222")
      (footprint "eagle-import:TO92")
      (libsource (lib "eagle-import") (part "-NPN-TO92"))
    )
    (comp (ref "T89")
      (value "2N2222")
      (footprint "eagle-import:TO92")
      (libsource (lib "eagle-import") (part "-NPN-TO92"))
    )
    (comp (ref "TAD")
      (value "BULB")
      (footprint "eagle-import:BULB")
      (libsource (lib "eagle-import") (part "BULB"))
    )
    (comp (ref "WORDCOUNT")
      (value "BULB")
      (footprint "eagle-import:BULB")
      (libsource (lib "eagle-import") (part "BULB"))
    )
    (comp (ref "C40")
      (value "MA17-2")
      (footprint "eagle-import:MA17-2")
      (libsource (lib "eagle-import") (part "MA17-2"))
    )
    (comp (ref "D40")
      (value "MA17-2")
      (footprint "eagle-import:MA17-2")
      (libsource (lib "eagle-import") (part "MA17-2"))
    )
    (comp (ref "E40")
      (value "MA17-2")
      (footprint "eagle-import:MA17-2")
      (libsource (lib "eagle-import") (part "MA17-2"))
    )
    (comp (ref "F40")
      (value "MA17-2")
      (footprint "eagle-import:MA17-2")
      (libsource (lib "eagle-import") (part "MA17-2"))
    )
  )
  (nets
    (net (code "1") (name "+15V") (class "Default")
      (node (ref "+V1") (pin "1") (pinfunction "1_1") (pintype "passive"))
      (node (ref "+V2") (pin "1") (pinfunction "1_1") (pintype "passive"))
      (node (ref "R1") (pin "1") (pinfunction "1_1") (pintype "passive"))
      (node (ref "R10") (pin "1") (pinfunction "1_1") (pintype "passive"))
      (node (ref "R11") (pin "1") (pinfunction "1_1") (pintype "passive"))
      (node (ref "R12") (pin "1") (pinfunction "1_1") (pintype "passive"))
      (node (ref "R13") (pin "1") (pinfunction "1_1") (pintype "passive"))
      (node (ref "R14") (pin "1") (pinfunction "1_1") (pintype "passive"))
      (node (ref "R15") (pin "1") (pinfunction "1_1") (pintype "passive"))
      (node (ref "R16") (pin "1") (pinfunction "1_1") (pintype "passive"))
      (node (ref "R17") (pin "1") (pinfunction "1_1") (pintype "passive"))
      (node (ref "R18") (pin "1") (pinfunction "1_1") (pintype "passive"))
      (node (ref "R19") (pin "1") (pinfunction "1_1") (pintype "passive"))
      (node (ref "R2") (pin "1") (pinfunction "1_1") (pintype "passive"))
      (node (ref "R20") (pin "1") (pinfunction "1_1") (pintype "passive"))
      (node (ref "R21") (pin "1") (pinfunction "1_1") (pintype "passive"))
      (node (ref "R22") (pin "1") (pinfunction "1_1") (pintype "passive"))
      (node (ref "R23") (pin "1") (pinfunction "1_1") (pintype "passive"))
      (node (ref "R24") (pin "1") (pinfunction "1_1") (pintype "passive"))
      (node (ref "R25") (pin "1") (pinfunction "1_1") (pintype "passive"))
      (node (ref "R26") (pin "1") (pinfunction "1_1") (pintype "passive"))
      (node (ref "R27") (pin "1") (pinfunction "1_1") (pintype "passive"))
      (node (ref "R28") (pin "1") (pinfunction "1_1") (pintype "passive"))
      (node (ref "R29") (pin "1") (pinfunction "1_1") (pintype "passive"))
      (node (ref "R3") (pin "1") (pinfunction "1_1") (pintype "passive"))
      (node (ref "R30") (pin "1") (pinfunction "1_1") (pintype "passive"))
      (node (ref "R31") (pin "1") (pinfunction "1_1") (pintype "passive"))
      (node (ref "R32") (pin "1") (pinfunction "1_1") (pintype "passive"))
      (node (ref "R33") (pin "1") (pinfunction "1_1") (pintype "passive"))
      (node (ref "R34") (pin "1") (pinfunction "1_1") (pintype "passive"))
      (node (ref "R35") (pin "1") (pinfunction "1_1") (pintype "passive"))
      (node (ref "R36") (pin "1") (pinfunction "1_1") (pintype "passive"))
      (node (ref "R37") (pin "1") (pinfunction "1_1") (pintype "passive"))
      (node (ref "R38") (pin "1") (pinfunction "1_1") (pintype "passive"))
      (node (ref "R39") (pin "1") (pinfunction "1_1") (pintype "passive"))
      (node (ref "R4") (pin "1") (pinfunction "1_1") (pintype "passive"))
      (node (ref "R40") (pin "1") (pinfunction "1_1") (pintype "passive"))
      (node (ref "R41") (pin "1") (pinfunction "1_1") (pintype "passive"))
      (node (ref "R42") (pin "1") (pinfunction "1_1") (pintype "passive"))
      (node (ref "R43") (pin "1") (pinfunction "1_1") (pintype "passive"))
      (node (ref "R44") (pin "1") (pinfunction "1_1") (pintype "passive"))
      (node (ref "R45") (pin "1") (pinfunction "1_1") (pintype "passive"))
      (node (ref "R46") (pin "1") (pinfunction "1_1") (pintype "passive"))
      (node (ref "R47") (pin "1") (pinfunction "1_1") (pintype "passive"))
      (node (ref "R48") (pin "1") (pinfunction "1_1") (pintype "passive"))
      (node (ref "R49") (pin "1") (pinfunction "1_1") (pintype "passive"))
      (node (ref "R5") (pin "1") (pinfunction "1_1") (pintype "passive"))
      (node (ref "R50") (pin "1") (pinfunction "1_1") (pintype "passive"))
      (node (ref "R51") (pin "1") (pinfunction "1_1") (pintype "passive"))
      (node (ref "R52") (pin "1") (pinfunction "1_1") (pintype "passive"))
      (node (ref "R53") (pin "1") (pinfunction "1_1") (pintype "passive"))
      (node (ref "R54") (pin "1") (pinfunction "1_1") (pintype "passive"))
      (node (ref "R55") (pin "1") (pinfunction "1_1") (pintype "passive"))
      (node (ref "R56") (pin "1") (pinfunction "1_1") (pintype "passive"))
      (node (ref "R57") (pin "1") (pinfunction "1_1") (pintype "passive"))
      (node (ref "R58") (pin "1") (pinfunction "1_1") (pintype "passive"))
      (node (ref "R59") (pin "1") (pinfunction "1_1") (pintype "passive"))
      (node (ref "R6") (pin "1") (pinfunction "1_1") (pintype "passive"))
      (node (ref "R60") (pin "1") (pinfunction "1_1") (pintype "passive"))
      (node (ref "R61") (pin "1") (pinfunction "1_1") (pintype "passive"))
      (node (ref "R62") (pin "1") (pinfunction "1_1") (pintype "passive"))
      (node (ref "R63") (pin "1") (pinfunction "1_1") (pintype "passive"))
      (node (ref "R64") (pin "1") (pinfunction "1_1") (pintype "passive"))
      (node (ref "R65") (pin "1") (pinfunction "1_1") (pintype "passive"))
      (node (ref "R66") (pin "1") (pinfunction "1_1") (pintype "passive"))
      (node (ref "R67") (pin "1") (pinfunction "1_1") (pintype "passive"))
      (node (ref "R68") (pin "1") (pinfunction "1_1") (pintype "passive"))
      (node (ref "R69") (pin "1") (pinfunction "1_1") (pintype "passive"))
      (node (ref "R7") (pin "1") (pinfunction "1_1") (pintype "passive"))
      (node (ref "R70") (pin "1") (pinfunction "1_1") (pintype "passive"))
      (node (ref "R71") (pin "1") (pinfunction "1_1") (pintype "passive"))
      (node (ref "R72") (pin "1") (pinfunction "1_1") (pintype "passive"))
      (node (ref "R73") (pin "1") (pinfunction "1_1") (pintype "passive"))
      (node (ref "R74") (pin "1") (pinfunction "1_1") (pintype "passive"))
      (node (ref "R75") (pin "1") (pinfunction "1_1") (pintype "passive"))
      (node (ref "R76") (pin "1") (pinfunction "1_1") (pintype "passive"))
      (node (ref "R77") (pin "1") (pinfunction "1_1") (pintype "passive"))
      (node (ref "R78") (pin "1") (pinfunction "1_1") (pintype "passive"))
      (node (ref "R79") (pin "1") (pinfunction "1_1") (pintype "passive"))
      (node (ref "R8") (pin "1") (pinfunction "1_1") (pintype "passive"))
      (node (ref "R80") (pin "1") (pinfunction "1_1") (pintype "passive"))
      (node (ref "R81") (pin "1") (pinfunction "1_1") (pintype "passive"))
      (node (ref "R82") (pin "1") (pinfunction "1_1") (pintype "passive"))
      (node (ref "R83") (pin "1") (pinfunction "1_1") (pintype "passive"))
      (node (ref "R84") (pin "1") (pinfunction "1_1") (pintype "passive"))
      (node (ref "R85") (pin "1") (pinfunction "1_1") (pintype "passive"))
      (node (ref "R86") (pin "1") (pinfunction "1_1") (pintype "passive"))
      (node (ref "R87") (pin "1") (pinfunction "1_1") (pintype "passive"))
      (node (ref "R88") (pin "1") (pinfunction "1_1") (pintype "passive"))
      (node (ref "R89") (pin "1") (pinfunction "1_1") (pintype "passive"))
      (node (ref "R9") (pin "1") (pinfunction "1_1") (pintype "passive"))
    )
    (net (code "2") (name "AC0") (class "Default")
      (node (ref "D40TOP") (pin "4") (pinfunction "1_4") (pintype "passive"))
      (node (ref "E40") (pin "7") (pinfunction "7_7") (pintype "passive"))
      (node (ref "T43") (pin "2") (pinfunction "B_2") (pintype "passive"))
    )
    (net (code "3") (name "AC1") (class "Default")
      (node (ref "D40BOT") (pin "2") (pinfunction "1_2") (pintype "passive"))
      (node (ref "E40") (pin "4") (pinfunction "4_4") (pintype "passive"))
      (node (ref "T44") (pin "2") (pinfunction "B_2") (pintype "passive"))
    )
    (net (code "4") (name "AC2") (class "Default")
      (node (ref "D40TOP") (pin "12") (pinfunction "1_12") (pintype "passive"))
      (node (ref "E40") (pin "21") (pinfunction "21_21") (pintype "passive"))
      (node (ref "T45") (pin "2") (pinfunction "B_2") (pintype "passive"))
    )
    (net (code "5") (name "AC3") (class "Default")
      (node (ref "D40BOT") (pin "9") (pinfunction "1_9") (pintype "passive"))
      (node (ref "E40") (pin "14") (pinfunction "14_14") (pintype "passive"))
      (node (ref "T46") (pin "2") (pinfunction "B_2") (pintype "passive"))
    )
    (net (code "6") (name "AC4") (class "Default")
      (node (ref "D40TOP") (pin "17") (pinfunction "1_17") (pintype "passive"))
      (node (ref "E40") (pin "31") (pinfunction "31_31") (pintype "passive"))
      (node (ref "T47") (pin "2") (pinfunction "B_2") (pintype "passive"))
    )
    (net (code "7") (name "AC5") (class "Default")
      (node (ref "D40BOT") (pin "16") (pinfunction "1_16") (pintype "passive"))
      (node (ref "E40") (pin "28") (pinfunction "28_28") (pintype "passive"))
      (node (ref "T48") (pin "2") (pinfunction "B_2") (pintype "passive"))
    )
    (net (code "8") (name "AC6") (class "Default")
      (node (ref "E40TOP") (pin "4") (pinfunction "1_4") (pintype "passive"))
      (node (ref "F40") (pin "7") (pinfunction "7_7") (pintype "passive"))
      (node (ref "T49") (pin "2") (pinfunction "B_2") (pintype "passive"))
    )
    (net (code "9") (name "AC7") (class "Default")
      (node (ref "E40BOT") (pin "2") (pinfunction "1_2") (pintype "passive"))
      (node (ref "F40") (pin "4") (pinfunction "4_4") (pintype "passive"))
      (node (ref "T50") (pin "2") (pinfunction "B_2") (pintype "passive"))
    )
    (net (code "10") (name "AC8") (class "Default")
      (node (ref "E40TOP") (pin "12") (pinfunction "1_12") (pintype "passive"))
      (node (ref "F40") (pin "21") (pinfunction "21_21") (pintype "passive"))
      (node (ref "T51") (pin "2") (pinfunction "B_2") (pintype "passive"))
    )
    (net (code "11") (name "AC9") (class "Default")
      (node (ref "E40BOT") (pin "9") (pinfunction "1_9") (pintype "passive"))
      (node (ref "F40") (pin "14") (pinfunction "14_14") (pintype "passive"))
      (node (ref "T52") (pin "2") (pinfunction "B_2") (pintype "passive"))
    )
    (net (code "12") (name "AC10") (class "Default")
      (node (ref "E40TOP") (pin "17") (pinfunction "1_17") (pintype "passive"))
      (node (ref "F40") (pin "31") (pinfunction "31_31") (pintype "passive"))
      (node (ref "T53") (pin "2") (pinfunction "B_2") (pintype "passive"))
    )
    (net (code "13") (name "AC11") (class "Default")
      (node (ref "E40BOT") (pin "16") (pinfunction "1_16") (pintype "passive"))
      (node (ref "F40") (pin "28") (pinfunction "28_28") (pintype "passive"))
      (node (ref "T54") (pin "2") (pinfunction "B_2") (pintype "passive"))
    )
    (net (code "14") (name "AND") (class "Default")
      (node (ref "D40") (pin "2") (pinfunction "2_2") (pintype "passive"))
      (node (ref "F40BOT") (pin "1") (pinfunction "1_1") (pintype "passive"))
      (node (ref "T82") (pin "2") (pinfunction "B_2") (pintype "passive"))
    )
    (net (code "15") (name "BREAK") (class "Default")
      (node (ref "D40") (pin "22") (pinfunction "22_22") (pintype "passive"))
      (node (ref "F40BOT") (pin "12") (pinfunction "1_12") (pintype "passive"))
      (node (ref "T81") (pin "2") (pinfunction "B_2") (pintype "passive"))
    )
    (net (code "16") (name "CA") (class "Default")
      (node (ref "D40") (pin "32") (pinfunction "32_32") (pintype "passive"))
      (node (ref "F40BOT") (pin "18") (pinfunction "1_18") (pintype "passive"))
      (node (ref "T80") (pin "2") (pinfunction "B_2") (pintype "passive"))
    )
    (net (code "17") (name "DCA") (class "Default")
      (node (ref "D40") (pin "8") (pinfunction "8_8") (pintype "passive"))
      (node (ref "F40BOT") (pin "4") (pinfunction "1_4") (pintype "passive"))
      (node (ref "T85") (pin "2") (pinfunction "B_2") (pintype "passive"))
    )
    (net (code "18") (name "DEFER") (class "Default")
      (node (ref "D40") (pin "26") (pinfunction "26_26") (pintype "passive"))
      (node (ref "F40BOT") (pin "15") (pinfunction "1_15") (pintype "passive"))
      (node (ref "T78") (pin "2") (pinfunction "B_2") (pintype "passive"))
    )
    (net (code "19") (name "DF0") (class "Default")
      (node (ref "C40") (pin "1") (pinfunction "1_1") (pintype "passive"))
      (node (ref "C40TOP") (pin "1") (pinfunction "1_1") (pintype "passive"))
      (node (ref "T1") (pin "2") (pinfunction "B_2") (pintype "passive"))
    )
    (net (code "20") (name "DF1") (class "Default")
      (node (ref "C40") (pin "10") (pinfunction "10_10") (pintype "passive"))
      (node (ref "C40BOT") (pin "5") (pinfunction "1_5") (pintype "passive"))
      (node (ref "T2") (pin "2") (pinfunction "B_2") (pintype "passive"))
    )
    (net (code "21") (name "DF2") (class "Default")
      (node (ref "C40") (pin "11") (pinfunction "11_11") (pintype "passive"))
      (node (ref "C40TOP") (pin "6") (pinfunction "1_6") (pintype "passive"))
      (node (ref "T3") (pin "2") (pinfunction "B_2") (pintype "passive"))
    )
    (net (code "22") (name "EXECUTE") (class "Default")
      (node (ref "D40") (pin "28") (pinfunction "28_28") (pintype "passive"))
      (node (ref "F40BOT") (pin "16") (pinfunction "1_16") (pintype "passive"))
      (node (ref "T77") (pin "2") (pinfunction "B_2") (pintype "passive"))
    )
    (net (code "23") (name "FETCH") (class "Default")
      (node (ref "D40") (pin "24") (pinfunction "24_24") (pintype "passive"))
      (node (ref "F40BOT") (pin "14") (pinfunction "1_14") (pintype "passive"))
      (node (ref "T76") (pin "2") (pinfunction "B_2") (pintype "passive"))
    )
    (net (code "24") (name "GND") (class "Default")
      (node (ref "C40") (pin "17") (pinfunction "17_17") (pintype "passive"))
      (node (ref "C40") (pin "18") (pinfunction "18_18") (pintype "passive"))
      (node (ref "C40") (pin "19") (pinfunction "19_19") (pintype "passive"))
      (node (ref "C40") (pin "20") (pinfunction "20_20") (pintype "passive"))
      (node (ref "C40BOT") (pin "13") (pinfunction "1_13") (pintype "passive"))
      (node (ref "D40") (pin "17") (pinfunction "17_17") (pintype "passive"))
      (node (ref "D40") (pin "18") (pinfunction "18_18") (pintype "passive"))
      (node (ref "D40") (pin "19") (pinfunction "19_19") (pintype "passive"))
      (node (ref "D40") (pin "20") (pinfunction "20_20") (pintype "passive"))
      (node (ref "D40BOT") (pin "13") (pinfunction "1_13") (pintype "passive"))
      (node (ref "E40") (pin "17") (pinfunction "17_17") (pintype "passive"))
      (node (ref "E40") (pin "18") (pinfunction "18_18") (pintype "passive"))
      (node (ref "E40") (pin "19") (pinfunction "19_19") (pintype "passive"))
      (node (ref "E40") (pin "20") (pinfunction "20_20") (pintype "passive"))
      (node (ref "E40BOT") (pin "13") (pinfunction "1_13") (pintype "passive"))
      (node (ref "F40") (pin "17") (pinfunction "17_17") (pintype "passive"))
      (node (ref "F40") (pin "18") (pinfunction "18_18") (pintype "passive"))
      (node (ref "F40") (pin "19") (pinfunction "19_19") (pintype "passive"))
      (node (ref "F40") (pin "20") (pinfunction "20_20") (pintype "passive"))
      (node (ref "F40BOT") (pin "13") (pinfunction "1_13") (pintype "passive"))
      (node (ref "GND1") (pin "1") (pinfunction "1_1") (pintype "passive"))
      (node (ref "GND2") (pin "1") (pinfunction "1_1") (pintype "passive"))
      (node (ref "T1") (pin "1") (pinfunction "E_1") (pintype "passive"))
      (node (ref "T10") (pin "1") (pinfunction "E_1") (pintype "passive"))
      (node (ref "T11") (pin "1") (pinfunction "E_1") (pintype "passive"))
      (node (ref "T12") (pin "1") (pinfunction "E_1") (pintype "passive"))
      (node (ref "T13") (pin "1") (pinfunction "E_1") (pintype "passive"))
      (node (ref "T14") (pin "1") (pinfunction "E_1") (pintype "passive"))
      (node (ref "T15") (pin "1") (pinfunction "E_1") (pintype "passive"))
      (node (ref "T16") (pin "1") (pinfunction "E_1") (pintype "passive"))
      (node (ref "T17") (pin "1") (pinfunction "E_1") (pintype "passive"))
      (node (ref "T18") (pin "1") (pinfunction "E_1") (pintype "passive"))
      (node (ref "T19") (pin "1") (pinfunction "E_1") (pintype "passive"))
      (node (ref "T2") (pin "1") (pinfunction "E_1") (pintype "passive"))
      (node (ref "T20") (pin "1") (pinfunction "E_1") (pintype "passive"))
      (node (ref "T21") (pin "1") (pinfunction "E_1") (pintype "passive"))
      (node (ref "T22") (pin "1") (pinfunction "E_1") (pintype "passive"))
      (node (ref "T23") (pin "1") (pinfunction "E_1") (pintype "passive"))
      (node (ref "T24") (pin "1") (pinfunction "E_1") (pintype "passive"))
      (node (ref "T25") (pin "1") (pinfunction "E_1") (pintype "passive"))
      (node (ref "T26") (pin "1") (pinfunction "E_1") (pintype "passive"))
      (node (ref "T27") (pin "1") (pinfunction "E_1") (pintype "passive"))
      (node (ref "T28") (pin "1") (pinfunction "E_1") (pintype "passive"))
      (node (ref "T29") (pin "1") (pinfunction "E_1") (pintype "passive"))
      (node (ref "T3") (pin "1") (pinfunction "E_1") (pintype "passive"))
      (node (ref "T30") (pin "1") (pinfunction "E_1") (pintype "passive"))
      (node (ref "T31") (pin "1") (pinfunction "E_1") (pintype "passive"))
      (node (ref "T32") (pin "1") (pinfunction "E_1") (pintype "passive"))
      (node (ref "T33") (pin "1") (pinfunction "E_1") (pintype "passive"))
      (node (ref "T34") (pin "1") (pinfunction "E_1") (pintype "passive"))
      (node (ref "T35") (pin "1") (pinfunction "E_1") (pintype "passive"))
      (node (ref "T36") (pin "1") (pinfunction "E_1") (pintype "passive"))
      (node (ref "T37") (pin "1") (pinfunction "E_1") (pintype "passive"))
      (node (ref "T38") (pin "1") (pinfunction "E_1") (pintype "passive"))
      (node (ref "T39") (pin "1") (pinfunction "E_1") (pintype "passive"))
      (node (ref "T4") (pin "1") (pinfunction "E_1") (pintype "passive"))
      (node (ref "T40") (pin "1") (pinfunction "E_1") (pintype "passive"))
      (node (ref "T41") (pin "1") (pinfunction "E_1") (pintype "passive"))
      (node (ref "T42") (pin "1") (pinfunction "E_1") (pintype "passive"))
      (node (ref "T43") (pin "1") (pinfunction "E_1") (pintype "passive"))
      (node (ref "T44") (pin "1") (pinfunction "E_1") (pintype "passive"))
      (node (ref "T45") (pin "1") (pinfunction "E_1") (pintype "passive"))
      (node (ref "T46") (pin "1") (pinfunction "E_1") (pintype "passive"))
      (node (ref "T47") (pin "1") (pinfunction "E_1") (pintype "passive"))
      (node (ref "T48") (pin "1") (pinfunction "E_1") (pintype "passive"))
      (node (ref "T49") (pin "1") (pinfunction "E_1") (pintype "passive"))
      (node (ref "T5") (pin "1") (pinfunction "E_1") (pintype "passive"))
      (node (ref "T50") (pin "1") (pinfunction "E_1") (pintype "passive"))
      (node (ref "T51") (pin "1") (pinfunction "E_1") (pintype "passive"))
      (node (ref "T52") (pin "1") (pinfunction "E_1") (pintype "passive"))
      (node (ref "T53") (pin "1") (pinfunction "E_1") (pintype "passive"))
      (node (ref "T54") (pin "1") (pinfunction "E_1") (pintype "passive"))
      (node (ref "T55") (pin "1") (pinfunction "E_1") (pintype "passive"))
      (node (ref "T56") (pin "1") (pinfunction "E_1") (pintype "passive"))
      (node (ref "T57") (pin "1") (pinfunction "E_1") (pintype "passive"))
      (node (ref "T58") (pin "1") (pinfunction "E_1") (pintype "passive"))
      (node (ref "T59") (pin "1") (pinfunction "E_1") (pintype "passive"))
      (node (ref "T6") (pin "1") (pinfunction "E_1") (pintype "passive"))
      (node (ref "T60") (pin "1") (pinfunction "E_1") (pintype "passive"))
      (node (ref "T61") (pin "1") (pinfunction "E_1") (pintype "passive"))
      (node (ref "T62") (pin "1") (pinfunction "E_1") (pintype "passive"))
      (node (ref "T63") (pin "1") (pinfunction "E_1") (pintype "passive"))
      (node (ref "T64") (pin "1") (pinfunction "E_1") (pintype "passive"))
      (node (ref "T65") (pin "1") (pinfunction "E_1") (pintype "passive"))
      (node (ref "T66") (pin "1") (pinfunction "E_1") (pintype "passive"))
      (node (ref "T67") (pin "1") (pinfunction "E_1") (pintype "passive"))
      (node (ref "T68") (pin "1") (pinfunction "E_1") (pintype "passive"))
      (node (ref "T69") (pin "1") (pinfunction "E_1") (pintype "passive"))
      (node (ref "T7") (pin "1") (pinfunction "E_1") (pintype "passive"))
      (node (ref "T70") (pin "1") (pinfunction "E_1") (pintype "passive"))
      (node (ref "T71") (pin "1") (pinfunction "E_1") (pintype "passive"))
      (node (ref "T72") (pin "1") (pinfunction "E_1") (pintype "passive"))
      (node (ref "T73") (pin "1") (pinfunction "E_1") (pintype "passive"))
      (node (ref "T74") (pin "1") (pinfunction "E_1") (pintype "passive"))
      (node (ref "T75") (pin "1") (pinfunction "E_1") (pintype "passive"))
      (node (ref "T76") (pin "1") (pinfunction "E_1") (pintype "passive"))
      (node (ref "T77") (pin "1") (pinfunction "E_1") (pintype "passive"))
      (node (ref "T78") (pin "1") (pinfunction "E_1") (pintype "passive"))
      (node (ref "T79") (pin "1") (pinfunction "E_1") (pintype "passive"))
      (node (ref "T8") (pin "1") (pinfunction "E_1") (pintype "passive"))
      (node (ref "T80") (pin "1") (pinfunction "E_1") (pintype "passive"))
      (node (ref "T81") (pin "1") (pinfunction "E_1") (pintype "passive"))
      (node (ref "T82") (pin "1") (pinfunction "E_1") (pintype "passive"))
      (node (ref "T83") (pin "1") (pinfunction "E_1") (pintype "passive"))
      (node (ref "T84") (pin "1") (pinfunction "E_1") (pintype "passive"))
      (node (ref "T85") (pin "1") (pinfunction "E_1") (pintype "passive"))
      (node (ref "T86") (pin "1") (pinfunction "E_1") (pintype "passive"))
      (node (ref "T87") (pin "1") (pinfunction "E_1") (pintype "passive"))
      (node (ref "T88") (pin "1") (pinfunction "E_1") (pintype "passive"))
      (node (ref "T89") (pin "1") (pinfunction "E_1") (pintype "passive"))
      (node (ref "T9") (pin "1") (pinfunction "E_1") (pintype "passive"))
    )
    (net (code "25") (name "IF0") (class "Default")
      (node (ref "C40") (pin "24") (pinfunction "24_24") (pintype "passive"))
      (node (ref "C40BOT") (pin "14") (pinfunction "1_14") (pintype "passive"))
      (node (ref "T4") (pin "2") (pinfunction "B_2") (pintype "passive"))
    )
    (net (code "26") (name "IF1") (class "Default")
      (node (ref "C40") (pin "25") (pinfunction "25_25") (pintype "passive"))
      (node (ref "C40TOP") (pin "14") (pinfunction "1_14") (pintype "passive"))
      (node (ref "T5") (pin "2") (pinfunction "B_2") (pintype "passive"))
    )
    (net (code "27") (name "IF2") (class "Default")
      (node (ref "C40") (pin "34") (pinfunction "34_34") (pintype "passive"))
      (node (ref "C40BOT") (pin "19") (pinfunction "1_19") (pintype "passive"))
      (node (ref "T6") (pin "2") (pinfunction "B_2") (pintype "passive"))
    )
    (net (code "28") (name "ION") (class "Default")
      (node (ref "D40") (pin "34") (pinfunction "34_34") (pintype "passive"))
      (node (ref "F40BOT") (pin "19") (pinfunction "1_19") (pintype "passive"))
      (node (ref "T73") (pin "2") (pinfunction "B_2") (pintype "passive"))
    )
    (net (code "29") (name "IOT") (class "Default")
      (node (ref "D40") (pin "23") (pinfunction "23_23") (pintype "passive"))
      (node (ref "F40TOP") (pin "13") (pinfunction "1_13") (pintype "passive"))
      (node (ref "T88") (pin "2") (pinfunction "B_2") (pintype "passive"))
    )
    (net (code "30") (name "ISZ") (class "Default")
      (node (ref "D40") (pin "6") (pinfunction "6_6") (pintype "passive"))
      (node (ref "F40BOT") (pin "3") (pinfunction "1_3") (pintype "passive"))
      (node (ref "T84") (pin "2") (pinfunction "B_2") (pintype "passive"))
    )
    (net (code "31") (name "JMP") (class "Default")
      (node (ref "D40") (pin "12") (pinfunction "12_12") (pintype "passive"))
      (node (ref "F40BOT") (pin "6") (pinfunction "1_6") (pintype "passive"))
      (node (ref "T87") (pin "2") (pinfunction "B_2") (pintype "passive"))
    )
    (net (code "32") (name "JMS") (class "Default")
      (node (ref "D40") (pin "10") (pinfunction "10_10") (pintype "passive"))
      (node (ref "F40BOT") (pin "5") (pinfunction "1_5") (pintype "passive"))
      (node (ref "T86") (pin "2") (pinfunction "B_2") (pintype "passive"))
    )
    (net (code "33") (name "LINK") (class "Default")
      (node (ref "C40") (pin "28") (pinfunction "28_28") (pintype "passive"))
      (node (ref "C40BOT") (pin "16") (pinfunction "1_16") (pintype "passive"))
      (node (ref "T72") (pin "2") (pinfunction "B_2") (pintype "passive"))
    )
    (net (code "34") (name "MA0") (class "Default")
      (node (ref "D40TOP") (pin "2") (pinfunction "1_2") (pintype "passive"))
      (node (ref "E40") (pin "3") (pinfunction "3_3") (pintype "passive"))
      (node (ref "T19") (pin "2") (pinfunction "B_2") (pintype "passive"))
    )
    (net (code "35") (name "MA1") (class "Default")
      (node (ref "D40BOT") (pin "4") (pinfunction "1_4") (pintype "passive"))
      (node (ref "E40") (pin "8") (pinfunction "8_8") (pintype "passive"))
      (node (ref "T20") (pin "2") (pinfunction "B_2") (pintype "passive"))
    )
    (net (code "36") (name "MA2") (class "Default")
      (node (ref "D40TOP") (pin "7") (pinfunction "1_7") (pintype "passive"))
      (node (ref "E40") (pin "13") (pinfunction "13_13") (pintype "passive"))
      (node (ref "T21") (pin "2") (pinfunction "B_2") (pintype "passive"))
    )
    (net (code "37") (name "MA3") (class "Default")
      (node (ref "D40BOT") (pin "12") (pinfunction "1_12") (pintype "passive"))
      (node (ref "E40") (pin "22") (pinfunction "22_22") (pintype "passive"))
      (node (ref "T22") (pin "2") (pinfunction "B_2") (pintype "passive"))
    )
    (net (code "38") (name "MA4") (class "Default")
      (node (ref "D40TOP") (pin "15") (pinfunction "1_15") (pintype "passive"))
      (node (ref "E40") (pin "27") (pinfunction "27_27") (pintype "passive"))
      (node (ref "T23") (pin "2") (pinfunction "B_2") (pintype "passive"))
    )
    (net (code "39") (name "MA5") (class "Default")
      (node (ref "D40BOT") (pin "18") (pinfunction "1_18") (pintype "passive"))
      (node (ref "E40") (pin "32") (pinfunction "32_32") (pintype "passive"))
      (node (ref "T24") (pin "2") (pinfunction "B_2") (pintype "passive"))
    )
    (net (code "40") (name "MA6") (class "Default")
      (node (ref "E40TOP") (pin "2") (pinfunction "1_2") (pintype "passive"))
      (node (ref "F40") (pin "3") (pinfunction "3_3") (pintype "passive"))
      (node (ref "T25") (pin "2") (pinfunction "B_2") (pintype "passive"))
    )
    (net (code "41") (name "MA7") (class "Default")
      (node (ref "E40BOT") (pin "4") (pinfunction "1_4") (pintype "passive"))
      (node (ref "F40") (pin "8") (pinfunction "8_8") (pintype "passive"))
      (node (ref "T26") (pin "2") (pinfunction "B_2") (pintype "passive"))
    )
    (net (code "42") (name "MA8") (class "Default")
      (node (ref "E40TOP") (pin "7") (pinfunction "1_7") (pintype "passive"))
      (node (ref "F40") (pin "13") (pinfunction "13_13") (pintype "passive"))
      (node (ref "T27") (pin "2") (pinfunction "B_2") (pintype "passive"))
    )
    (net (code "43") (name "MA9") (class "Default")
      (node (ref "E40BOT") (pin "12") (pinfunction "1_12") (pintype "passive"))
      (node (ref "F40") (pin "22") (pinfunction "22_22") (pintype "passive"))
      (node (ref "T28") (pin "2") (pinfunction "B_2") (pintype "passive"))
    )
    (net (code "44") (name "MA10") (class "Default")
      (node (ref "E40TOP") (pin "15") (pinfunction "1_15") (pintype "passive"))
      (node (ref "F40") (pin "27") (pinfunction "27_27") (pintype "passive"))
      (node (ref "T29") (pin "2") (pinfunction "B_2") (pintype "passive"))
    )
    (net (code "45") (name "MA11") (class "Default")
      (node (ref "E40BOT") (pin "18") (pinfunction "1_18") (pintype "passive"))
      (node (ref "F40") (pin "32") (pinfunction "32_32") (pintype "passive"))
      (node (ref "T30") (pin "2") (pinfunction "B_2") (pintype "passive"))
    )
    (net (code "46") (name "MB0") (class "Default")
      (node (ref "D40TOP") (pin "3") (pinfunction "1_3") (pintype "passive"))
      (node (ref "E40") (pin "5") (pinfunction "5_5") (pintype "passive"))
      (node (ref "T31") (pin "2") (pinfunction "B_2") (pintype "passive"))
    )
    (net (code "47") (name "MB1") (class "Default")
      (node (ref "D40BOT") (pin "3") (pinfunction "1_3") (pintype "passive"))
      (node (ref "E40") (pin "6") (pinfunction "6_6") (pintype "passive"))
      (node (ref "T32") (pin "2") (pinfunction "B_2") (pintype "passive"))
    )
    (net (code "48") (name "MB2") (class "Default")
      (node (ref "D40TOP") (pin "8") (pinfunction "1_8") (pintype "passive"))
      (node (ref "E40") (pin "15") (pinfunction "15_15") (pintype "passive"))
      (node (ref "T33") (pin "2") (pinfunction "B_2") (pintype "passive"))
    )
    (net (code "49") (name "MB3") (class "Default")
      (node (ref "D40BOT") (pin "11") (pinfunction "1_11") (pintype "passive"))
      (node (ref "E40") (pin "16") (pinfunction "16_16") (pintype "passive"))
      (node (ref "T34") (pin "2") (pinfunction "B_2") (pintype "passive"))
    )
    (net (code "50") (name "MB4") (class "Default")
      (node (ref "D40TOP") (pin "16") (pinfunction "1_16") (pintype "passive"))
      (node (ref "E40") (pin "29") (pinfunction "29_29") (pintype "passive"))
      (node (ref "T35") (pin "2") (pinfunction "B_2") (pintype "passive"))
    )
    (net (code "51") (name "MB5") (class "Default")
      (node (ref "D40BOT") (pin "17") (pinfunction "1_17") (pintype "passive"))
      (node (ref "E40") (pin "30") (pinfunction "30_30") (pintype "passive"))
      (node (ref "T36") (pin "2") (pinfunction "B_2") (pintype "passive"))
    )
    (net (code "52") (name "MB6") (class "Default")
      (node (ref "E40TOP") (pin "3") (pinfunction "1_3") (pintype "passive"))
      (node (ref "F40") (pin "5") (pinfunction "5_5") (pintype "passive"))
      (node (ref "T37") (pin "2") (pinfunction "B_2") (pintype "passive"))
    )
    (net (code "53") (name "MB7") (class "Default")
      (node (ref "E40BOT") (pin "3") (pinfunction "1_3") (pintype "passive"))
      (node (ref "F40") (pin "6") (pinfunction "6_6") (pintype "passive"))
      (node (ref "T38") (pin "2") (pinfunction "B_2") (pintype "passive"))
    )
    (net (code "54") (name "MB8") (class "Default")
      (node (ref "E40TOP") (pin "8") (pinfunction "1_8") (pintype "passive"))
      (node (ref "F40") (pin "15") (pinfunction "15_15") (pintype "passive"))
      (node (ref "T39") (pin "2") (pinfunction "B_2") (pintype "passive"))
    )
    (net (code "55") (name "MB9") (class "Default")
      (node (ref "E40BOT") (pin "11") (pinfunction "1_11") (pintype "passive"))
      (node (ref "F40") (pin "16") (pinfunction "16_16") (pintype "passive"))
      (node (ref "T40") (pin "2") (pinfunction "B_2") (pintype "passive"))
    )
    (net (code "56") (name "MB10") (class "Default")
      (node (ref "E40TOP") (pin "16") (pinfunction "1_16") (pintype "passive"))
      (node (ref "F40") (pin "29") (pinfunction "29_29") (pintype "passive"))
      (node (ref "T41") (pin "2") (pinfunction "B_2") (pintype "passive"))
    )
    (net (code "57") (name "MB11") (class "Default")
      (node (ref "E40BOT") (pin "17") (pinfunction "1_17") (pintype "passive"))
      (node (ref "F40") (pin "30") (pinfunction "30_30") (pintype "passive"))
      (node (ref "T42") (pin "2") (pinfunction "B_2") (pintype "passive"))
    )
    (net (code "58") (name "MQ0") (class "Default")
      (node (ref "D40TOP") (pin "5") (pinfunction "1_5") (pintype "passive"))
      (node (ref "E40") (pin "9") (pinfunction "9_9") (pintype "passive"))
      (node (ref "T55") (pin "2") (pinfunction "B_2") (pintype "passive"))
    )
    (net (code "59") (name "MQ1") (class "Default")
      (node (ref "D40BOT") (pin "1") (pinfunction "1_1") (pintype "passive"))
      (node (ref "E40") (pin "2") (pinfunction "2_2") (pintype "passive"))
      (node (ref "T56") (pin "2") (pinfunction "B_2") (pintype "passive"))
    )
    (net (code "60") (name "MQ2") (class "Default")
      (node (ref "D40TOP") (pin "13") (pinfunction "1_13") (pintype "passive"))
      (node (ref "E40") (pin "23") (pinfunction "23_23") (pintype "passive"))
      (node (ref "T57") (pin "2") (pinfunction "B_2") (pintype "passive"))
    )
    (net (code "61") (name "MQ3") (class "Default")
      (node (ref "D40BOT") (pin "6") (pinfunction "1_6") (pintype "passive"))
      (node (ref "E40") (pin "12") (pinfunction "12_12") (pintype "passive"))
      (node (ref "T58") (pin "2") (pinfunction "B_2") (pintype "passive"))
    )
    (net (code "62") (name "MQ4") (class "Default")
      (node (ref "D40TOP") (pin "18") (pinfunction "1_18") (pintype "passive"))
      (node (ref "E40") (pin "33") (pinfunction "33_33") (pintype "passive"))
      (node (ref "T59") (pin "2") (pinfunction "B_2") (pintype "passive"))
    )
    (net (code "63") (name "MQ5") (class "Default")
      (node (ref "D40BOT") (pin "15") (pinfunction "1_15") (pintype "passive"))
      (node (ref "E40") (pin "26") (pinfunction "26_26") (pintype "passive"))
      (node (ref "T60") (pin "2") (pinfunction "B_2") (pintype "passive"))
    )
    (net (code "64") (name "MQ6") (class "Default")
      (node (ref "E40TOP") (pin "5") (pinfunction "1_5") (pintype "passive"))
      (node (ref "F40") (pin "9") (pinfunction "9_9") (pintype "passive"))
      (node (ref "T61") (pin "2") (pinfunction "B_2") (pintype "passive"))
    )
    (net (code "65") (name "MQ7") (class "Default")
      (node (ref "E40BOT") (pin "1") (pinfunction "1_1") (pintype "passive"))
      (node (ref "F40") (pin "2") (pinfunction "2_2") (pintype "passive"))
      (node (ref "T62") (pin "2") (pinfunction "B_2") (pintype "passive"))
    )
    (net (code "66") (name "MQ8") (class "Default")
      (node (ref "E40TOP") (pin "13") (pinfunction "1_13") (pintype "passive"))
      (node (ref "F40") (pin "23") (pinfunction "23_23") (pintype "passive"))
      (node (ref "T63") (pin "2") (pinfunction "B_2") (pintype "passive"))
    )
    (net (code "67") (name "MQ9") (class "Default")
      (node (ref "E40BOT") (pin "6") (pinfunction "1_6") (pintype "passive"))
      (node (ref "F40") (pin "12") (pinfunction "12_12") (pintype "passive"))
      (node (ref "T64") (pin "2") (pinfunction "B_2") (pintype "passive"))
    )
    (net (code "68") (name "MQ10") (class "Default")
      (node (ref "E40TOP") (pin "18") (pinfunction "1_18") (pintype "passive"))
      (node (ref "F40") (pin "33") (pinfunction "33_33") (pintype "passive"))
      (node (ref "T65") (pin "2") (pinfunction "B_2") (pintype "passive"))
    )
    (net (code "69") (name "MQ11") (class "Default")
      (node (ref "E40BOT") (pin "15") (pinfunction "1_15") (pintype "passive"))
      (node (ref "F40") (pin "26") (pinfunction "26_26") (pintype "passive"))
      (node (ref "T66") (pin "2") (pinfunction "B_2") (pintype "passive"))
    )
    (net (code "70") (name "Net-(AC0-PadA)") (class "Default")
      (node (ref "AC0") (pin "A") (pinfunction "A_A") (pintype "passive"))
      (node (ref "R43") (pin "2") (pinfunction "2_2") (pintype "passive"))
    )
    (net (code "71") (name "Net-(AC1-PadA)") (class "Default")
      (node (ref "AC1") (pin "A") (pinfunction "A_A") (pintype "passive"))
      (node (ref "R44") (pin "2") (pinfunction "2_2") (pintype "passive"))
    )
    (net (code "72") (name "Net-(AC2-PadA)") (class "Default")
      (node (ref "AC2") (pin "A") (pinfunction "A_A") (pintype "passive"))
      (node (ref "R45") (pin "2") (pinfunction "2_2") (pintype "passive"))
    )
    (net (code "73") (name "Net-(AC3-PadA)") (class "Default")
      (node (ref "AC3") (pin "A") (pinfunction "A_A") (pintype "passive"))
      (node (ref "R46") (pin "2") (pinfunction "2_2") (pintype "passive"))
    )
    (net (code "74") (name "Net-(AC4-PadA)") (class "Default")
      (node (ref "AC4") (pin "A") (pinfunction "A_A") (pintype "passive"))
      (node (ref "R47") (pin "2") (pinfunction "2_2") (pintype "passive"))
    )
    (net (code "75") (name "Net-(AC5-PadA)") (class "Default")
      (node (ref "AC5") (pin "A") (pinfunction "A_A") (pintype "passive"))
      (node (ref "R48") (pin "2") (pinfunction "2_2") (pintype "passive"))
    )
    (net (code "76") (name "Net-(AC6-PadA)") (class "Default")
      (node (ref "AC6") (pin "A") (pinfunction "A_A") (pintype "passive"))
      (node (ref "R49") (pin "2") (pinfunction "2_2") (pintype "passive"))
    )
    (net (code "77") (name "Net-(AC7-PadA)") (class "Default")
      (node (ref "AC7") (pin "A") (pinfunction "A_A") (pintype "passive"))
      (node (ref "R50") (pin "2") (pinfunction "2_2") (pintype "passive"))
    )
    (net (code "78") (name "Net-(AC8-PadA)") (class "Default")
      (node (ref "AC8") (pin "A") (pinfunction "A_A") (pintype "passive"))
      (node (ref "R51") (pin "2") (pinfunction "2_2") (pintype "passive"))
    )
    (net (code "79") (name "Net-(AC9-PadA)") (class "Default")
      (node (ref "AC9") (pin "A") (pinfunction "A_A") (pintype "passive"))
      (node (ref "R52") (pin "2") (pinfunction "2_2") (pintype "passive"))
    )
    (net (code "80") (name "Net-(AC10-PadA)") (class "Default")
      (node (ref "AC10") (pin "A") (pinfunction "A_A") (pintype "passive"))
      (node (ref "R53") (pin "2") (pinfunction "2_2") (pintype "passive"))
    )
    (net (code "81") (name "Net-(AC11-PadA)") (class "Default")
      (node (ref "AC11") (pin "A") (pinfunction "A_A") (pintype "passive"))
      (node (ref "R54") (pin "2") (pinfunction "2_2") (pintype "passive"))
    )
    (net (code "82") (name "Net-(AND-PadA)") (class "Default")
      (node (ref "AND") (pin "A") (pinfunction "A_A") (pintype "passive"))
      (node (ref "R82") (pin "2") (pinfunction "2_2") (pintype "passive"))
    )
    (net (code "83") (name "Net-(BREAK-PadA)") (class "Default")
      (node (ref "BREAK") (pin "A") (pinfunction "A_A") (pintype "passive"))
      (node (ref "R81") (pin "2") (pinfunction "2_2") (pintype "passive"))
    )
    (net (code "84") (name "Net-(CURRENTADDRESS-PadA)") (class "Default")
      (node (ref "CURRENTADDRESS") (pin "A") (pinfunction "A_A") (pintype "passive"))
      (node (ref "R80") (pin "2") (pinfunction "2_2") (pintype "passive"))
    )
    (net (code "85") (name "Net-(DCA-PadA)") (class "Default")
      (node (ref "DCA") (pin "A") (pinfunction "A_A") (pintype "passive"))
      (node (ref "R85") (pin "2") (pinfunction "2_2") (pintype "passive"))
    )
    (net (code "86") (name "Net-(DEFER-PadA)") (class "Default")
      (node (ref "DEFER") (pin "A") (pinfunction "A_A") (pintype "passive"))
      (node (ref "R78") (pin "2") (pinfunction "2_2") (pintype "passive"))
    )
    (net (code "87") (name "Net-(DF0-PadA)") (class "Default")
      (node (ref "DF0") (pin "A") (pinfunction "A_A") (pintype "passive"))
      (node (ref "R1") (pin "2") (pinfunction "2_2") (pintype "passive"))
    )
    (net (code "88") (name "Net-(DF1-PadA)") (class "Default")
      (node (ref "DF1") (pin "A") (pinfunction "A_A") (pintype "passive"))
      (node (ref "R2") (pin "2") (pinfunction "2_2") (pintype "passive"))
    )
    (net (code "89") (name "Net-(DF2-PadA)") (class "Default")
      (node (ref "DF2") (pin "A") (pinfunction "A_A") (pintype "passive"))
      (node (ref "R3") (pin "2") (pinfunction "2_2") (pintype "passive"))
    )
    (net (code "90") (name "Net-(EXECUTE-PadA)") (class "Default")
      (node (ref "EXECUTE") (pin "A") (pinfunction "A_A") (pintype "passive"))
      (node (ref "R77") (pin "2") (pinfunction "2_2") (pintype "passive"))
    )
    (net (code "91") (name "Net-(FETCH-PadA)") (class "Default")
      (node (ref "FETCH") (pin "A") (pinfunction "A_A") (pintype "passive"))
      (node (ref "R76") (pin "2") (pinfunction "2_2") (pintype "passive"))
    )
    (net (code "92") (name "Net-(IF0-PadA)") (class "Default")
      (node (ref "IF0") (pin "A") (pinfunction "A_A") (pintype "passive"))
      (node (ref "R4") (pin "2") (pinfunction "2_2") (pintype "passive"))
    )
    (net (code "93") (name "Net-(IF1-PadA)") (class "Default")
      (node (ref "IF1") (pin "A") (pinfunction "A_A") (pintype "passive"))
      (node (ref "R5") (pin "2") (pinfunction "2_2") (pintype "passive"))
    )
    (net (code "94") (name "Net-(IF2-PadA)") (class "Default")
      (node (ref "IF2") (pin "A") (pinfunction "A_A") (pintype "passive"))
      (node (ref "R6") (pin "2") (pinfunction "2_2") (pintype "passive"))
    )
    (net (code "95") (name "Net-(ION-PadA)") (class "Default")
      (node (ref "ION") (pin "A") (pinfunction "A_A") (pintype "passive"))
      (node (ref "R73") (pin "2") (pinfunction "2_2") (pintype "passive"))
    )
    (net (code "96") (name "Net-(IOT-PadA)") (class "Default")
      (node (ref "IOT") (pin "A") (pinfunction "A_A") (pintype "passive"))
      (node (ref "R88") (pin "2") (pinfunction "2_2") (pintype "passive"))
    )
    (net (code "97") (name "Net-(ISZ-PadA)") (class "Default")
      (node (ref "ISZ") (pin "A") (pinfunction "A_A") (pintype "passive"))
      (node (ref "R84") (pin "2") (pinfunction "2_2") (pintype "passive"))
    )
    (net (code "98") (name "Net-(JMP-PadA)") (class "Default")
      (node (ref "JMP") (pin "A") (pinfunction "A_A") (pintype "passive"))
      (node (ref "R87") (pin "2") (pinfunction "2_2") (pintype "passive"))
    )
    (net (code "99") (name "Net-(JMS-PadA)") (class "Default")
      (node (ref "JMS") (pin "A") (pinfunction "A_A") (pintype "passive"))
      (node (ref "R86") (pin "2") (pinfunction "2_2") (pintype "passive"))
    )
    (net (code "100") (name "Net-(LINK-PadA)") (class "Default")
      (node (ref "LINK") (pin "A") (pinfunction "A_A") (pintype "passive"))
      (node (ref "R72") (pin "2") (pinfunction "2_2") (pintype "passive"))
    )
    (net (code "101") (name "Net-(MA0-PadA)") (class "Default")
      (node (ref "MA0") (pin "A") (pinfunction "A_A") (pintype "passive"))
      (node (ref "R19") (pin "2") (pinfunction "2_2") (pintype "passive"))
    )
    (net (code "102") (name "Net-(MA1-PadA)") (class "Default")
      (node (ref "MA1") (pin "A") (pinfunction "A_A") (pintype "passive"))
      (node (ref "R20") (pin "2") (pinfunction "2_2") (pintype "passive"))
    )
    (net (code "103") (name "Net-(MA2-PadA)") (class "Default")
      (node (ref "MA2") (pin "A") (pinfunction "A_A") (pintype "passive"))
      (node (ref "R21") (pin "2") (pinfunction "2_2") (pintype "passive"))
    )
    (net (code "104") (name "Net-(MA3-PadA)") (class "Default")
      (node (ref "MA3") (pin "A") (pinfunction "A_A") (pintype "passive"))
      (node (ref "R22") (pin "2") (pinfunction "2_2") (pintype "passive"))
    )
    (net (code "105") (name "Net-(MA4-PadA)") (class "Default")
      (node (ref "MA4") (pin "A") (pinfunction "A_A") (pintype "passive"))
      (node (ref "R23") (pin "2") (pinfunction "2_2") (pintype "passive"))
    )
    (net (code "106") (name "Net-(MA5-PadA)") (class "Default")
      (node (ref "MA5") (pin "A") (pinfunction "A_A") (pintype "passive"))
      (node (ref "R24") (pin "2") (pinfunction "2_2") (pintype "passive"))
    )
    (net (code "107") (name "Net-(MA6-PadA)") (class "Default")
      (node (ref "MA6") (pin "A") (pinfunction "A_A") (pintype "passive"))
      (node (ref "R25") (pin "2") (pinfunction "2_2") (pintype "passive"))
    )
    (net (code "108") (name "Net-(MA7-PadA)") (class "Default")
      (node (ref "MA7") (pin "A") (pinfunction "A_A") (pintype "passive"))
      (node (ref "R26") (pin "2") (pinfunction "2_2") (pintype "passive"))
    )
    (net (code "109") (name "Net-(MA8-PadA)") (class "Default")
      (node (ref "MA8") (pin "A") (pinfunction "A_A") (pintype "passive"))
      (node (ref "R27") (pin "2") (pinfunction "2_2") (pintype "passive"))
    )
    (net (code "110") (name "Net-(MA9-PadA)") (class "Default")
      (node (ref "MA9") (pin "A") (pinfunction "A_A") (pintype "passive"))
      (node (ref "R28") (pin "2") (pinfunction "2_2") (pintype "passive"))
    )
    (net (code "111") (name "Net-(MA10-PadA)") (class "Default")
      (node (ref "MA10") (pin "A") (pinfunction "A_A") (pintype "passive"))
      (node (ref "R29") (pin "2") (pinfunction "2_2") (pintype "passive"))
    )
    (net (code "112") (name "Net-(MA11-PadA)") (class "Default")
      (node (ref "MA11") (pin "A") (pinfunction "A_A") (pintype "passive"))
      (node (ref "R30") (pin "2") (pinfunction "2_2") (pintype "passive"))
    )
    (net (code "113") (name "Net-(MB0-PadA)") (class "Default")
      (node (ref "MB0") (pin "A") (pinfunction "A_A") (pintype "passive"))
      (node (ref "R31") (pin "2") (pinfunction "2_2") (pintype "passive"))
    )
    (net (code "114") (name "Net-(MB1-PadA)") (class "Default")
      (node (ref "MB1") (pin "A") (pinfunction "A_A") (pintype "passive"))
      (node (ref "R32") (pin "2") (pinfunction "2_2") (pintype "passive"))
    )
    (net (code "115") (name "Net-(MB2-PadA)") (class "Default")
      (node (ref "MB2") (pin "A") (pinfunction "A_A") (pintype "passive"))
      (node (ref "R33") (pin "2") (pinfunction "2_2") (pintype "passive"))
    )
    (net (code "116") (name "Net-(MB3-PadA)") (class "Default")
      (node (ref "MB3") (pin "A") (pinfunction "A_A") (pintype "passive"))
      (node (ref "R34") (pin "2") (pinfunction "2_2") (pintype "passive"))
    )
    (net (code "117") (name "Net-(MB4-PadA)") (class "Default")
      (node (ref "MB4") (pin "A") (pinfunction "A_A") (pintype "passive"))
      (node (ref "R35") (pin "2") (pinfunction "2_2") (pintype "passive"))
    )
    (net (code "118") (name "Net-(MB5-PadA)") (class "Default")
      (node (ref "MB5") (pin "A") (pinfunction "A_A") (pintype "passive"))
      (node (ref "R36") (pin "2") (pinfunction "2_2") (pintype "passive"))
    )
    (net (code "119") (name "Net-(MB6-PadA)") (class "Default")
      (node (ref "MB6") (pin "A") (pinfunction "A_A") (pintype "passive"))
      (node (ref "R37") (pin "2") (pinfunction "2_2") (pintype "passive"))
    )
    (net (code "120") (name "Net-(MB7-PadA)") (class "Default")
      (node (ref "MB7") (pin "A") (pinfunction "A_A") (pintype "passive"))
      (node (ref "R38") (pin "2") (pinfunction "2_2") (pintype "passive"))
    )
    (net (code "121") (name "Net-(MB8-PadA)") (class "Default")
      (node (ref "MB8") (pin "A") (pinfunction "A_A") (pintype "passive"))
      (node (ref "R39") (pin "2") (pinfunction "2_2") (pintype "passive"))
    )
    (net (code "122") (name "Net-(MB9-PadA)") (class "Default")
      (node (ref "MB9") (pin "A") (pinfunction "A_A") (pintype "passive"))
      (node (ref "R40") (pin "2") (pinfunction "2_2") (pintype "passive"))
    )
    (net (code "123") (name "Net-(MB10-PadA)") (class "Default")
      (node (ref "MB10") (pin "A") (pinfunction "A_A") (pintype "passive"))
      (node (ref "R41") (pin "2") (pinfunction "2_2") (pintype "passive"))
    )
    (net (code "124") (name "Net-(MB11-PadA)") (class "Default")
      (node (ref "MB11") (pin "A") (pinfunction "A_A") (pintype "passive"))
      (node (ref "R42") (pin "2") (pinfunction "2_2") (pintype "passive"))
    )
    (net (code "125") (name "Net-(MQ0-PadA)") (class "Default")
      (node (ref "MQ0") (pin "A") (pinfunction "A_A") (pintype "passive"))
      (node (ref "R55") (pin "2") (pinfunction "2_2") (pintype "passive"))
    )
    (net (code "126") (name "Net-(MQ1-PadA)") (class "Default")
      (node (ref "MQ1") (pin "A") (pinfunction "A_A") (pintype "passive"))
      (node (ref "R56") (pin "2") (pinfunction "2_2") (pintype "passive"))
    )
    (net (code "127") (name "Net-(MQ2-PadA)") (class "Default")
      (node (ref "MQ2") (pin "A") (pinfunction "A_A") (pintype "passive"))
      (node (ref "R57") (pin "2") (pinfunction "2_2") (pintype "passive"))
    )
    (net (code "128") (name "Net-(MQ3-PadA)") (class "Default")
      (node (ref "MQ3") (pin "A") (pinfunction "A_A") (pintype "passive"))
      (node (ref "R58") (pin "2") (pinfunction "2_2") (pintype "passive"))
    )
    (net (code "129") (name "Net-(MQ4-PadA)") (class "Default")
      (node (ref "MQ4") (pin "A") (pinfunction "A_A") (pintype "passive"))
      (node (ref "R59") (pin "2") (pinfunction "2_2") (pintype "passive"))
    )
    (net (code "130") (name "Net-(MQ5-PadA)") (class "Default")
      (node (ref "MQ5") (pin "A") (pinfunction "A_A") (pintype "passive"))
      (node (ref "R60") (pin "2") (pinfunction "2_2") (pintype "passive"))
    )
    (net (code "131") (name "Net-(MQ6-PadA)") (class "Default")
      (node (ref "MQ6") (pin "A") (pinfunction "A_A") (pintype "passive"))
      (node (ref "R61") (pin "2") (pinfunction "2_2") (pintype "passive"))
    )
    (net (code "132") (name "Net-(MQ7-PadA)") (class "Default")
      (node (ref "MQ7") (pin "A") (pinfunction "A_A") (pintype "passive"))
      (node (ref "R62") (pin "2") (pinfunction "2_2") (pintype "passive"))
    )
    (net (code "133") (name "Net-(MQ8-PadA)") (class "Default")
      (node (ref "MQ8") (pin "A") (pinfunction "A_A") (pintype "passive"))
      (node (ref "R63") (pin "2") (pinfunction "2_2") (pintype "passive"))
    )
    (net (code "134") (name "Net-(MQ9-PadA)") (class "Default")
      (node (ref "MQ9") (pin "A") (pinfunction "A_A") (pintype "passive"))
      (node (ref "R64") (pin "2") (pinfunction "2_2") (pintype "passive"))
    )
    (net (code "135") (name "Net-(MQ10-PadA)") (class "Default")
      (node (ref "MQ10") (pin "A") (pinfunction "A_A") (pintype "passive"))
      (node (ref "R65") (pin "2") (pinfunction "2_2") (pintype "passive"))
    )
    (net (code "136") (name "Net-(MQ11-PadA)") (class "Default")
      (node (ref "MQ11") (pin "A") (pinfunction "A_A") (pintype "passive"))
      (node (ref "R66") (pin "2") (pinfunction "2_2") (pintype "passive"))
    )
    (net (code "137") (name "Net-(OPR-PadA)") (class "Default")
      (node (ref "OPR") (pin "A") (pinfunction "A_A") (pintype "passive"))
      (node (ref "R89") (pin "2") (pinfunction "2_2") (pintype "passive"))
    )
    (net (code "138") (name "Net-(PAUSE-PadA)") (class "Default")
      (node (ref "PAUSE") (pin "A") (pinfunction "A_A") (pintype "passive"))
      (node (ref "R74") (pin "2") (pinfunction "2_2") (pintype "passive"))
    )
    (net (code "139") (name "Net-(PC0-PadA)") (class "Default")
      (node (ref "PC0") (pin "A") (pinfunction "A_A") (pintype "passive"))
      (node (ref "R7") (pin "2") (pinfunction "2_2") (pintype "passive"))
    )
    (net (code "140") (name "Net-(PC1-PadA)") (class "Default")
      (node (ref "PC1") (pin "A") (pinfunction "A_A") (pintype "passive"))
      (node (ref "R8") (pin "2") (pinfunction "2_2") (pintype "passive"))
    )
    (net (code "141") (name "Net-(PC2-PadA)") (class "Default")
      (node (ref "PC2") (pin "A") (pinfunction "A_A") (pintype "passive"))
      (node (ref "R9") (pin "2") (pinfunction "2_2") (pintype "passive"))
    )
    (net (code "142") (name "Net-(PC3-PadA)") (class "Default")
      (node (ref "PC3") (pin "A") (pinfunction "A_A") (pintype "passive"))
      (node (ref "R10") (pin "2") (pinfunction "2_2") (pintype "passive"))
    )
    (net (code "143") (name "Net-(PC4-PadA)") (class "Default")
      (node (ref "PC4") (pin "A") (pinfunction "A_A") (pintype "passive"))
      (node (ref "R11") (pin "2") (pinfunction "2_2") (pintype "passive"))
    )
    (net (code "144") (name "Net-(PC5-PadA)") (class "Default")
      (node (ref "PC5") (pin "A") (pinfunction "A_A") (pintype "passive"))
      (node (ref "R12") (pin "2") (pinfunction "2_2") (pintype "passive"))
    )
    (net (code "145") (name "Net-(PC6-PadA)") (class "Default")
      (node (ref "PC6") (pin "A") (pinfunction "A_A") (pintype "passive"))
      (node (ref "R13") (pin "2") (pinfunction "2_2") (pintype "passive"))
    )
    (net (code "146") (name "Net-(PC7-PadA)") (class "Default")
      (node (ref "PC7") (pin "A") (pinfunction "A_A") (pintype "passive"))
      (node (ref "R14") (pin "2") (pinfunction "2_2") (pintype "passive"))
    )
    (net (code "147") (name "Net-(PC8-PadA)") (class "Default")
      (node (ref "PC8") (pin "A") (pinfunction "A_A") (pintype "passive"))
      (node (ref "R15") (pin "2") (pinfunction "2_2") (pintype "passive"))
    )
    (net (code "148") (name "Net-(PC9-PadA)") (class "Default")
      (node (ref "PC9") (pin "A") (pinfunction "A_A") (pintype "passive"))
      (node (ref "R16") (pin "2") (pinfunction "2_2") (pintype "passive"))
    )
    (net (code "149") (name "Net-(PC10-PadA)") (class "Default")
      (node (ref "PC10") (pin "A") (pinfunction "A_A") (pintype "passive"))
      (node (ref "R17") (pin "2") (pinfunction "2_2") (pintype "passive"))
    )
    (net (code "150") (name "Net-(PC11-PadA)") (class "Default")
      (node (ref "PC11") (pin "A") (pinfunction "A_A") (pintype "passive"))
      (node (ref "R18") (pin "2") (pinfunction "2_2") (pintype "passive"))
    )
    (net (code "151") (name "Net-(R67-Pad2)") (class "Default")
      (node (ref "R67") (pin "2") (pinfunction "2_2") (pintype "passive"))
      (node (ref "SC0") (pin "A") (pinfunction "A_A") (pintype "passive"))
    )
    (net (code "152") (name "Net-(R68-Pad2)") (class "Default")
      (node (ref "R68") (pin "2") (pinfunction "2_2") (pintype "passive"))
      (node (ref "SC1") (pin "A") (pinfunction "A_A") (pintype "passive"))
    )
    (net (code "153") (name "Net-(R69-Pad2)") (class "Default")
      (node (ref "R69") (pin "2") (pinfunction "2_2") (pintype "passive"))
      (node (ref "SC2") (pin "A") (pinfunction "A_A") (pintype "passive"))
    )
    (net (code "154") (name "Net-(R70-Pad2)") (class "Default")
      (node (ref "R70") (pin "2") (pinfunction "2_2") (pintype "passive"))
      (node (ref "SC3") (pin "A") (pinfunction "A_A") (pintype "passive"))
    )
    (net (code "155") (name "Net-(R71-Pad2)") (class "Default")
      (node (ref "R71") (pin "2") (pinfunction "2_2") (pintype "passive"))
      (node (ref "SC4") (pin "A") (pinfunction "A_A") (pintype "passive"))
    )
    (net (code "156") (name "Net-(R75-Pad2)") (class "Default")
      (node (ref "R75") (pin "2") (pinfunction "2_2") (pintype "passive"))
      (node (ref "RUN") (pin "A") (pinfunction "A_A") (pintype "passive"))
    )
    (net (code "157") (name "Net-(R79-Pad2)") (class "Default")
      (node (ref "R79") (pin "2") (pinfunction "2_2") (pintype "passive"))
      (node (ref "WORDCOUNT") (pin "A") (pinfunction "A_A") (pintype "passive"))
    )
    (net (code "158") (name "Net-(R83-Pad2)") (class "Default")
      (node (ref "R83") (pin "2") (pinfunction "2_2") (pintype "passive"))
      (node (ref "TAD") (pin "A") (pinfunction "A_A") (pintype "passive"))
    )
    (net (code "159") (name "Net-(T1-C)") (class "Default")
      (node (ref "DF0") (pin "B") (pinfunction "B_B") (pintype "passive"))
      (node (ref "T1") (pin "3") (pinfunction "C_3") (pintype "passive"))
    )
    (net (code "160") (name "Net-(T2-C)") (class "Default")
      (node (ref "DF1") (pin "B") (pinfunction "B_B") (pintype "passive"))
      (node (ref "T2") (pin "3") (pinfunction "C_3") (pintype "passive"))
    )
    (net (code "161") (name "Net-(T3-C)") (class "Default")
      (node (ref "DF2") (pin "B") (pinfunction "B_B") (pintype "passive"))
      (node (ref "T3") (pin "3") (pinfunction "C_3") (pintype "passive"))
    )
    (net (code "162") (name "Net-(T4-C)") (class "Default")
      (node (ref "IF0") (pin "B") (pinfunction "B_B") (pintype "passive"))
      (node (ref "T4") (pin "3") (pinfunction "C_3") (pintype "passive"))
    )
    (net (code "163") (name "Net-(T5-C)") (class "Default")
      (node (ref "IF1") (pin "B") (pinfunction "B_B") (pintype "passive"))
      (node (ref "T5") (pin "3") (pinfunction "C_3") (pintype "passive"))
    )
    (net (code "164") (name "Net-(T6-C)") (class "Default")
      (node (ref "IF2") (pin "B") (pinfunction "B_B") (pintype "passive"))
      (node (ref "T6") (pin "3") (pinfunction "C_3") (pintype "passive"))
    )
    (net (code "165") (name "Net-(T7-C)") (class "Default")
      (node (ref "PC0") (pin "B") (pinfunction "B_B") (pintype "passive"))
      (node (ref "T7") (pin "3") (pinfunction "C_3") (pintype "passive"))
    )
    (net (code "166") (name "Net-(T8-C)") (class "Default")
      (node (ref "PC1") (pin "B") (pinfunction "B_B") (pintype "passive"))
      (node (ref "T8") (pin "3") (pinfunction "C_3") (pintype "passive"))
    )
    (net (code "167") (name "Net-(T9-C)") (class "Default")
      (node (ref "PC2") (pin "B") (pinfunction "B_B") (pintype "passive"))
      (node (ref "T9") (pin "3") (pinfunction "C_3") (pintype "passive"))
    )
    (net (code "168") (name "Net-(T10-C)") (class "Default")
      (node (ref "PC3") (pin "B") (pinfunction "B_B") (pintype "passive"))
      (node (ref "T10") (pin "3") (pinfunction "C_3") (pintype "passive"))
    )
    (net (code "169") (name "Net-(T11-C)") (class "Default")
      (node (ref "PC4") (pin "B") (pinfunction "B_B") (pintype "passive"))
      (node (ref "T11") (pin "3") (pinfunction "C_3") (pintype "passive"))
    )
    (net (code "170") (name "Net-(T12-C)") (class "Default")
      (node (ref "PC5") (pin "B") (pinfunction "B_B") (pintype "passive"))
      (node (ref "T12") (pin "3") (pinfunction "C_3") (pintype "passive"))
    )
    (net (code "171") (name "Net-(T13-C)") (class "Default")
      (node (ref "PC6") (pin "B") (pinfunction "B_B") (pintype "passive"))
      (node (ref "T13") (pin "3") (pinfunction "C_3") (pintype "passive"))
    )
    (net (code "172") (name "Net-(T14-C)") (class "Default")
      (node (ref "PC7") (pin "B") (pinfunction "B_B") (pintype "passive"))
      (node (ref "T14") (pin "3") (pinfunction "C_3") (pintype "passive"))
    )
    (net (code "173") (name "Net-(T15-C)") (class "Default")
      (node (ref "PC8") (pin "B") (pinfunction "B_B") (pintype "passive"))
      (node (ref "T15") (pin "3") (pinfunction "C_3") (pintype "passive"))
    )
    (net (code "174") (name "Net-(T16-C)") (class "Default")
      (node (ref "PC9") (pin "B") (pinfunction "B_B") (pintype "passive"))
      (node (ref "T16") (pin "3") (pinfunction "C_3") (pintype "passive"))
    )
    (net (code "175") (name "Net-(T17-C)") (class "Default")
      (node (ref "PC10") (pin "B") (pinfunction "B_B") (pintype "passive"))
      (node (ref "T17") (pin "3") (pinfunction "C_3") (pintype "passive"))
    )
    (net (code "176") (name "Net-(T18-C)") (class "Default")
      (node (ref "PC11") (pin "B") (pinfunction "B_B") (pintype "passive"))
      (node (ref "T18") (pin "3") (pinfunction "C_3") (pintype "passive"))
    )
    (net (code "177") (name "Net-(T19-C)") (class "Default")
      (node (ref "MA0") (pin "B") (pinfunction "B_B") (pintype "passive"))
      (node (ref "T19") (pin "3") (pinfunction "C_3") (pintype "passive"))
    )
    (net (code "178") (name "Net-(T20-C)") (class "Default")
      (node (ref "MA1") (pin "B") (pinfunction "B_B") (pintype "passive"))
      (node (ref "T20") (pin "3") (pinfunction "C_3") (pintype "passive"))
    )
    (net (code "179") (name "Net-(T21-C)") (class "Default")
      (node (ref "MA2") (pin "B") (pinfunction "B_B") (pintype "passive"))
      (node (ref "T21") (pin "3") (pinfunction "C_3") (pintype "passive"))
    )
    (net (code "180") (name "Net-(T22-C)") (class "Default")
      (node (ref "MA3") (pin "B") (pinfunction "B_B") (pintype "passive"))
      (node (ref "T22") (pin "3") (pinfunction "C_3") (pintype "passive"))
    )
    (net (code "181") (name "Net-(T23-C)") (class "Default")
      (node (ref "MA4") (pin "B") (pinfunction "B_B") (pintype "passive"))
      (node (ref "T23") (pin "3") (pinfunction "C_3") (pintype "passive"))
    )
    (net (code "182") (name "Net-(T24-C)") (class "Default")
      (node (ref "MA5") (pin "B") (pinfunction "B_B") (pintype "passive"))
      (node (ref "T24") (pin "3") (pinfunction "C_3") (pintype "passive"))
    )
    (net (code "183") (name "Net-(T25-C)") (class "Default")
      (node (ref "MA6") (pin "B") (pinfunction "B_B") (pintype "passive"))
      (node (ref "T25") (pin "3") (pinfunction "C_3") (pintype "passive"))
    )
    (net (code "184") (name "Net-(T26-C)") (class "Default")
      (node (ref "MA7") (pin "B") (pinfunction "B_B") (pintype "passive"))
      (node (ref "T26") (pin "3") (pinfunction "C_3") (pintype "passive"))
    )
    (net (code "185") (name "Net-(T27-C)") (class "Default")
      (node (ref "MA8") (pin "B") (pinfunction "B_B") (pintype "passive"))
      (node (ref "T27") (pin "3") (pinfunction "C_3") (pintype "passive"))
    )
    (net (code "186") (name "Net-(T28-C)") (class "Default")
      (node (ref "MA9") (pin "B") (pinfunction "B_B") (pintype "passive"))
      (node (ref "T28") (pin "3") (pinfunction "C_3") (pintype "passive"))
    )
    (net (code "187") (name "Net-(T29-C)") (class "Default")
      (node (ref "MA10") (pin "B") (pinfunction "B_B") (pintype "passive"))
      (node (ref "T29") (pin "3") (pinfunction "C_3") (pintype "passive"))
    )
    (net (code "188") (name "Net-(T30-C)") (class "Default")
      (node (ref "MA11") (pin "B") (pinfunction "B_B") (pintype "passive"))
      (node (ref "T30") (pin "3") (pinfunction "C_3") (pintype "passive"))
    )
    (net (code "189") (name "Net-(T31-C)") (class "Default")
      (node (ref "MB0") (pin "B") (pinfunction "B_B") (pintype "passive"))
      (node (ref "T31") (pin "3") (pinfunction "C_3") (pintype "passive"))
    )
    (net (code "190") (name "Net-(T32-C)") (class "Default")
      (node (ref "MB1") (pin "B") (pinfunction "B_B") (pintype "passive"))
      (node (ref "T32") (pin "3") (pinfunction "C_3") (pintype "passive"))
    )
    (net (code "191") (name "Net-(T33-C)") (class "Default")
      (node (ref "MB2") (pin "B") (pinfunction "B_B") (pintype "passive"))
      (node (ref "T33") (pin "3") (pinfunction "C_3") (pintype "passive"))
    )
    (net (code "192") (name "Net-(T34-C)") (class "Default")
      (node (ref "MB3") (pin "B") (pinfunction "B_B") (pintype "passive"))
      (node (ref "T34") (pin "3") (pinfunction "C_3") (pintype "passive"))
    )
    (net (code "193") (name "Net-(T35-C)") (class "Default")
      (node (ref "MB4") (pin "B") (pinfunction "B_B") (pintype "passive"))
      (node (ref "T35") (pin "3") (pinfunction "C_3") (pintype "passive"))
    )
    (net (code "194") (name "Net-(T36-C)") (class "Default")
      (node (ref "MB5") (pin "B") (pinfunction "B_B") (pintype "passive"))
      (node (ref "T36") (pin "3") (pinfunction "C_3") (pintype "passive"))
    )
    (net (code "195") (name "Net-(T37-C)") (class "Default")
      (node (ref "MB6") (pin "B") (pinfunction "B_B") (pintype "passive"))
      (node (ref "T37") (pin "3") (pinfunction "C_3") (pintype "passive"))
    )
    (net (code "196") (name "Net-(T38-C)") (class "Default")
      (node (ref "MB7") (pin "B") (pinfunction "B_B") (pintype "passive"))
      (node (ref "T38") (pin "3") (pinfunction "C_3") (pintype "passive"))
    )
    (net (code "197") (name "Net-(T39-C)") (class "Default")
      (node (ref "MB8") (pin "B") (pinfunction "B_B") (pintype "passive"))
      (node (ref "T39") (pin "3") (pinfunction "C_3") (pintype "passive"))
    )
    (net (code "198") (name "Net-(T40-C)") (class "Default")
      (node (ref "MB9") (pin "B") (pinfunction "B_B") (pintype "passive"))
      (node (ref "T40") (pin "3") (pinfunction "C_3") (pintype "passive"))
    )
    (net (code "199") (name "Net-(T41-C)") (class "Default")
      (node (ref "MB10") (pin "B") (pinfunction "B_B") (pintype "passive"))
      (node (ref "T41") (pin "3") (pinfunction "C_3") (pintype "passive"))
    )
    (net (code "200") (name "Net-(T42-C)") (class "Default")
      (node (ref "MB11") (pin "B") (pinfunction "B_B") (pintype "passive"))
      (node (ref "T42") (pin "3") (pinfunction "C_3") (pintype "passive"))
    )
    (net (code "201") (name "Net-(T43-C)") (class "Default")
      (node (ref "AC0") (pin "B") (pinfunction "B_B") (pintype "passive"))
      (node (ref "T43") (pin "3") (pinfunction "C_3") (pintype "passive"))
    )
    (net (code "202") (name "Net-(T44-C)") (class "Default")
      (node (ref "AC1") (pin "B") (pinfunction "B_B") (pintype "passive"))
      (node (ref "T44") (pin "3") (pinfunction "C_3") (pintype "passive"))
    )
    (net (code "203") (name "Net-(T45-C)") (class "Default")
      (node (ref "AC2") (pin "B") (pinfunction "B_B") (pintype "passive"))
      (node (ref "T45") (pin "3") (pinfunction "C_3") (pintype "passive"))
    )
    (net (code "204") (name "Net-(T46-C)") (class "Default")
      (node (ref "AC3") (pin "B") (pinfunction "B_B") (pintype "passive"))
      (node (ref "T46") (pin "3") (pinfunction "C_3") (pintype "passive"))
    )
    (net (code "205") (name "Net-(T47-C)") (class "Default")
      (node (ref "AC4") (pin "B") (pinfunction "B_B") (pintype "passive"))
      (node (ref "T47") (pin "3") (pinfunction "C_3") (pintype "passive"))
    )
    (net (code "206") (name "Net-(T48-C)") (class "Default")
      (node (ref "AC5") (pin "B") (pinfunction "B_B") (pintype "passive"))
      (node (ref "T48") (pin "3") (pinfunction "C_3") (pintype "passive"))
    )
    (net (code "207") (name "Net-(T49-C)") (class "Default")
      (node (ref "AC6") (pin "B") (pinfunction "B_B") (pintype "passive"))
      (node (ref "T49") (pin "3") (pinfunction "C_3") (pintype "passive"))
    )
    (net (code "208") (name "Net-(T50-C)") (class "Default")
      (node (ref "AC7") (pin "B") (pinfunction "B_B") (pintype "passive"))
      (node (ref "T50") (pin "3") (pinfunction "C_3") (pintype "passive"))
    )
    (net (code "209") (name "Net-(T51-C)") (class "Default")
      (node (ref "AC8") (pin "B") (pinfunction "B_B") (pintype "passive"))
      (node (ref "T51") (pin "3") (pinfunction "C_3") (pintype "passive"))
    )
    (net (code "210") (name "Net-(T52-C)") (class "Default")
      (node (ref "AC9") (pin "B") (pinfunction "B_B") (pintype "passive"))
      (node (ref "T52") (pin "3") (pinfunction "C_3") (pintype "passive"))
    )
    (net (code "211") (name "Net-(T53-C)") (class "Default")
      (node (ref "AC10") (pin "B") (pinfunction "B_B") (pintype "passive"))
      (node (ref "T53") (pin "3") (pinfunction "C_3") (pintype "passive"))
    )
    (net (code "212") (name "Net-(T54-C)") (class "Default")
      (node (ref "AC11") (pin "B") (pinfunction "B_B") (pintype "passive"))
      (node (ref "T54") (pin "3") (pinfunction "C_3") (pintype "passive"))
    )
    (net (code "213") (name "Net-(T55-C)") (class "Default")
      (node (ref "MQ0") (pin "B") (pinfunction "B_B") (pintype "passive"))
      (node (ref "T55") (pin "3") (pinfunction "C_3") (pintype "passive"))
    )
    (net (code "214") (name "Net-(T56-C)") (class "Default")
      (node (ref "MQ1") (pin "B") (pinfunction "B_B") (pintype "passive"))
      (node (ref "T56") (pin "3") (pinfunction "C_3") (pintype "passive"))
    )
    (net (code "215") (name "Net-(T57-C)") (class "Default")
      (node (ref "MQ2") (pin "B") (pinfunction "B_B") (pintype "passive"))
      (node (ref "T57") (pin "3") (pinfunction "C_3") (pintype "passive"))
    )
    (net (code "216") (name "Net-(T58-C)") (class "Default")
      (node (ref "MQ3") (pin "B") (pinfunction "B_B") (pintype "passive"))
      (node (ref "T58") (pin "3") (pinfunction "C_3") (pintype "passive"))
    )
    (net (code "217") (name "Net-(T59-C)") (class "Default")
      (node (ref "MQ4") (pin "B") (pinfunction "B_B") (pintype "passive"))
      (node (ref "T59") (pin "3") (pinfunction "C_3") (pintype "passive"))
    )
    (net (code "218") (name "Net-(T60-C)") (class "Default")
      (node (ref "MQ5") (pin "B") (pinfunction "B_B") (pintype "passive"))
      (node (ref "T60") (pin "3") (pinfunction "C_3") (pintype "passive"))
    )
    (net (code "219") (name "Net-(T61-C)") (class "Default")
      (node (ref "MQ6") (pin "B") (pinfunction "B_B") (pintype "passive"))
      (node (ref "T61") (pin "3") (pinfunction "C_3") (pintype "passive"))
    )
    (net (code "220") (name "Net-(T62-C)") (class "Default")
      (node (ref "MQ7") (pin "B") (pinfunction "B_B") (pintype "passive"))
      (node (ref "T62") (pin "3") (pinfunction "C_3") (pintype "passive"))
    )
    (net (code "221") (name "Net-(T63-C)") (class "Default")
      (node (ref "MQ8") (pin "B") (pinfunction "B_B") (pintype "passive"))
      (node (ref "T63") (pin "3") (pinfunction "C_3") (pintype "passive"))
    )
    (net (code "222") (name "Net-(T64-C)") (class "Default")
      (node (ref "MQ9") (pin "B") (pinfunction "B_B") (pintype "passive"))
      (node (ref "T64") (pin "3") (pinfunction "C_3") (pintype "passive"))
    )
    (net (code "223") (name "Net-(T65-C)") (class "Default")
      (node (ref "MQ10") (pin "B") (pinfunction "B_B") (pintype "passive"))
      (node (ref "T65") (pin "3") (pinfunction "C_3") (pintype "passive"))
    )
    (net (code "224") (name "Net-(T66-C)") (class "Default")
      (node (ref "MQ11") (pin "B") (pinfunction "B_B") (pintype "passive"))
      (node (ref "T66") (pin "3") (pinfunction "C_3") (pintype "passive"))
    )
    (net (code "225") (name "Net-(T67-C)") (class "Default")
      (node (ref "SC0") (pin "B") (pinfunction "B_B") (pintype "passive"))
      (node (ref "T67") (pin "3") (pinfunction "C_3") (pintype "passive"))
    )
    (net (code "226") (name "Net-(T68-C)") (class "Default")
      (node (ref "SC1") (pin "B") (pinfunction "B_B") (pintype "passive"))
      (node (ref "T68") (pin "3") (pinfunction "C_3") (pintype "passive"))
    )
    (net (code "227") (name "Net-(T69-C)") (class "Default")
      (node (ref "SC2") (pin "B") (pinfunction "B_B") (pintype "passive"))
      (node (ref "T69") (pin "3") (pinfunction "C_3") (pintype "passive"))
    )
    (net (code "228") (name "Net-(T70-C)") (class "Default")
      (node (ref "SC3") (pin "B") (pinfunction "B_B") (pintype "passive"))
      (node (ref "T70") (pin "3") (pinfunction "C_3") (pintype "passive"))
    )
    (net (code "229") (name "Net-(T71-C)") (class "Default")
      (node (ref "SC4") (pin "B") (pinfunction "B_B") (pintype "passive"))
      (node (ref "T71") (pin "3") (pinfunction "C_3") (pintype "passive"))
    )
    (net (code "230") (name "Net-(T72-C)") (class "Default")
      (node (ref "LINK") (pin "B") (pinfunction "B_B") (pintype "passive"))
      (node (ref "T72") (pin "3") (pinfunction "C_3") (pintype "passive"))
    )
    (net (code "231") (name "Net-(T73-C)") (class "Default")
      (node (ref "ION") (pin "B") (pinfunction "B_B") (pintype "passive"))
      (node (ref "T73") (pin "3") (pinfunction "C_3") (pintype "passive"))
    )
    (net (code "232") (name "Net-(T74-C)") (class "Default")
      (node (ref "PAUSE") (pin "B") (pinfunction "B_B") (pintype "passive"))
      (node (ref "T74") (pin "3") (pinfunction "C_3") (pintype "passive"))
    )
    (net (code "233") (name "Net-(T75-C)") (class "Default")
      (node (ref "RUN") (pin "B") (pinfunction "B_B") (pintype "passive"))
      (node (ref "T75") (pin "3") (pinfunction "C_3") (pintype "passive"))
    )
    (net (code "234") (name "Net-(T76-C)") (class "Default")
      (node (ref "FETCH") (pin "B") (pinfunction "B_B") (pintype "passive"))
      (node (ref "T76") (pin "3") (pinfunction "C_3") (pintype "passive"))
    )
    (net (code "235") (name "Net-(T77-C)") (class "Default")
      (node (ref "EXECUTE") (pin "B") (pinfunction "B_B") (pintype "passive"))
      (node (ref "T77") (pin "3") (pinfunction "C_3") (pintype "passive"))
    )
    (net (code "236") (name "Net-(T78-C)") (class "Default")
      (node (ref "DEFER") (pin "B") (pinfunction "B_B") (pintype "passive"))
      (node (ref "T78") (pin "3") (pinfunction "C_3") (pintype "passive"))
    )
    (net (code "237") (name "Net-(T79-C)") (class "Default")
      (node (ref "T79") (pin "3") (pinfunction "C_3") (pintype "passive"))
      (node (ref "WORDCOUNT") (pin "B") (pinfunction "B_B") (pintype "passive"))
    )
    (net (code "238") (name "Net-(T80-C)") (class "Default")
      (node (ref "CURRENTADDRESS") (pin "B") (pinfunction "B_B") (pintype "passive"))
      (node (ref "T80") (pin "3") (pinfunction "C_3") (pintype "passive"))
    )
    (net (code "239") (name "Net-(T81-C)") (class "Default")
      (node (ref "BREAK") (pin "B") (pinfunction "B_B") (pintype "passive"))
      (node (ref "T81") (pin "3") (pinfunction "C_3") (pintype "passive"))
    )
    (net (code "240") (name "Net-(T82-C)") (class "Default")
      (node (ref "AND") (pin "B") (pinfunction "B_B") (pintype "passive"))
      (node (ref "T82") (pin "3") (pinfunction "C_3") (pintype "passive"))
    )
    (net (code "241") (name "Net-(T83-C)") (class "Default")
      (node (ref "T83") (pin "3") (pinfunction "C_3") (pintype "passive"))
      (node (ref "TAD") (pin "B") (pinfunction "B_B") (pintype "passive"))
    )
    (net (code "242") (name "Net-(T84-C)") (class "Default")
      (node (ref "ISZ") (pin "B") (pinfunction "B_B") (pintype "passive"))
      (node (ref "T84") (pin "3") (pinfunction "C_3") (pintype "passive"))
    )
    (net (code "243") (name "Net-(T85-C)") (class "Default")
      (node (ref "DCA") (pin "B") (pinfunction "B_B") (pintype "passive"))
      (node (ref "T85") (pin "3") (pinfunction "C_3") (pintype "passive"))
    )
    (net (code "244") (name "Net-(T86-C)") (class "Default")
      (node (ref "JMS") (pin "B") (pinfunction "B_B") (pintype "passive"))
      (node (ref "T86") (pin "3") (pinfunction "C_3") (pintype "passive"))
    )
    (net (code "245") (name "Net-(T87-C)") (class "Default")
      (node (ref "JMP") (pin "B") (pinfunction "B_B") (pintype "passive"))
      (node (ref "T87") (pin "3") (pinfunction "C_3") (pintype "passive"))
    )
    (net (code "246") (name "Net-(T88-C)") (class "Default")
      (node (ref "IOT") (pin "B") (pinfunction "B_B") (pintype "passive"))
      (node (ref "T88") (pin "3") (pinfunction "C_3") (pintype "passive"))
    )
    (net (code "247") (name "Net-(T89-C)") (class "Default")
      (node (ref "OPR") (pin "B") (pinfunction "B_B") (pintype "passive"))
      (node (ref "T89") (pin "3") (pinfunction "C_3") (pintype "passive"))
    )
    (net (code "248") (name "OPR") (class "Default")
      (node (ref "D40") (pin "16") (pinfunction "16_16") (pintype "passive"))
      (node (ref "F40BOT") (pin "11") (pinfunction "1_11") (pintype "passive"))
      (node (ref "T89") (pin "2") (pinfunction "B_2") (pintype "passive"))
    )
    (net (code "249") (name "PAUSE") (class "Default")
      (node (ref "D40") (pin "31") (pinfunction "31_31") (pintype "passive"))
      (node (ref "F40TOP") (pin "17") (pinfunction "1_17") (pintype "passive"))
      (node (ref "T74") (pin "2") (pinfunction "B_2") (pintype "passive"))
    )
    (net (code "250") (name "PC0") (class "Default")
      (node (ref "D40TOP") (pin "1") (pinfunction "1_1") (pintype "passive"))
      (node (ref "E40") (pin "1") (pinfunction "1_1") (pintype "passive"))
      (node (ref "T7") (pin "2") (pinfunction "B_2") (pintype "passive"))
    )
    (net (code "251") (name "PC1") (class "Default")
      (node (ref "D40BOT") (pin "5") (pinfunction "1_5") (pintype "passive"))
      (node (ref "E40") (pin "10") (pinfunction "10_10") (pintype "passive"))
      (node (ref "T8") (pin "2") (pinfunction "B_2") (pintype "passive"))
    )
    (net (code "252") (name "PC2") (class "Default")
      (node (ref "D40TOP") (pin "6") (pinfunction "1_6") (pintype "passive"))
      (node (ref "E40") (pin "11") (pinfunction "11_11") (pintype "passive"))
      (node (ref "T9") (pin "2") (pinfunction "B_2") (pintype "passive"))
    )
    (net (code "253") (name "PC3") (class "Default")
      (node (ref "D40BOT") (pin "14") (pinfunction "1_14") (pintype "passive"))
      (node (ref "E40") (pin "24") (pinfunction "24_24") (pintype "passive"))
      (node (ref "T10") (pin "2") (pinfunction "B_2") (pintype "passive"))
    )
    (net (code "254") (name "PC4") (class "Default")
      (node (ref "D40TOP") (pin "14") (pinfunction "1_14") (pintype "passive"))
      (node (ref "E40") (pin "25") (pinfunction "25_25") (pintype "passive"))
      (node (ref "T11") (pin "2") (pinfunction "B_2") (pintype "passive"))
    )
    (net (code "255") (name "PC5") (class "Default")
      (node (ref "D40BOT") (pin "19") (pinfunction "1_19") (pintype "passive"))
      (node (ref "E40") (pin "34") (pinfunction "34_34") (pintype "passive"))
      (node (ref "T12") (pin "2") (pinfunction "B_2") (pintype "passive"))
    )
    (net (code "256") (name "PC6") (class "Default")
      (node (ref "E40TOP") (pin "1") (pinfunction "1_1") (pintype "passive"))
      (node (ref "F40") (pin "1") (pinfunction "1_1") (pintype "passive"))
      (node (ref "T13") (pin "2") (pinfunction "B_2") (pintype "passive"))
    )
    (net (code "257") (name "PC7") (class "Default")
      (node (ref "E40BOT") (pin "5") (pinfunction "1_5") (pintype "passive"))
      (node (ref "F40") (pin "10") (pinfunction "10_10") (pintype "passive"))
      (node (ref "T14") (pin "2") (pinfunction "B_2") (pintype "passive"))
    )
    (net (code "258") (name "PC8") (class "Default")
      (node (ref "E40TOP") (pin "6") (pinfunction "1_6") (pintype "passive"))
      (node (ref "F40") (pin "11") (pinfunction "11_11") (pintype "passive"))
      (node (ref "T15") (pin "2") (pinfunction "B_2") (pintype "passive"))
    )
    (net (code "259") (name "PC9") (class "Default")
      (node (ref "E40BOT") (pin "14") (pinfunction "1_14") (pintype "passive"))
      (node (ref "F40") (pin "24") (pinfunction "24_24") (pintype "passive"))
      (node (ref "T16") (pin "2") (pinfunction "B_2") (pintype "passive"))
    )
    (net (code "260") (name "PC10") (class "Default")
      (node (ref "E40TOP") (pin "14") (pinfunction "1_14") (pintype "passive"))
      (node (ref "F40") (pin "25") (pinfunction "25_25") (pintype "passive"))
      (node (ref "T17") (pin "2") (pinfunction "B_2") (pintype "passive"))
    )
    (net (code "261") (name "PC11") (class "Default")
      (node (ref "E40BOT") (pin "19") (pinfunction "1_19") (pintype "passive"))
      (node (ref "F40") (pin "34") (pinfunction "34_34") (pintype "passive"))
      (node (ref "T18") (pin "2") (pinfunction "B_2") (pintype "passive"))
    )
    (net (code "262") (name "RUN") (class "Default")
      (node (ref "D40") (pin "33") (pinfunction "33_33") (pintype "passive"))
      (node (ref "F40TOP") (pin "18") (pinfunction "1_18") (pintype "passive"))
      (node (ref "T75") (pin "2") (pinfunction "B_2") (pintype "passive"))
    )
    (net (code "263") (name "SC0") (class "Default")
      (node (ref "C40") (pin "9") (pinfunction "9_9") (pintype "passive"))
      (node (ref "C40TOP") (pin "5") (pinfunction "1_5") (pintype "passive"))
      (node (ref "T67") (pin "2") (pinfunction "B_2") (pintype "passive"))
    )
    (net (code "264") (name "SC1") (class "Default")
      (node (ref "C40") (pin "2") (pinfunction "2_2") (pintype "passive"))
      (node (ref "C40BOT") (pin "1") (pinfunction "1_1") (pintype "passive"))
      (node (ref "T68") (pin "2") (pinfunction "B_2") (pintype "passive"))
    )
    (net (code "265") (name "SC2") (class "Default")
      (node (ref "C40") (pin "23") (pinfunction "23_23") (pintype "passive"))
      (node (ref "C40TOP") (pin "13") (pinfunction "1_13") (pintype "passive"))
      (node (ref "T69") (pin "2") (pinfunction "B_2") (pintype "passive"))
    )
    (net (code "266") (name "SC3") (class "Default")
      (node (ref "C40") (pin "12") (pinfunction "12_12") (pintype "passive"))
      (node (ref "C40BOT") (pin "6") (pinfunction "1_6") (pintype "passive"))
      (node (ref "T70") (pin "2") (pinfunction "B_2") (pintype "passive"))
    )
    (net (code "267") (name "SC4") (class "Default")
      (node (ref "C40") (pin "33") (pinfunction "33_33") (pintype "passive"))
      (node (ref "C40TOP") (pin "18") (pinfunction "1_18") (pintype "passive"))
      (node (ref "T71") (pin "2") (pinfunction "B_2") (pintype "passive"))
    )
    (net (code "268") (name "TAD") (class "Default")
      (node (ref "D40") (pin "4") (pinfunction "4_4") (pintype "passive"))
      (node (ref "F40BOT") (pin "2") (pinfunction "1_2") (pintype "passive"))
      (node (ref "T83") (pin "2") (pinfunction "B_2") (pintype "passive"))
    )
    (net (code "269") (name "WC") (class "Default")
      (node (ref "D40") (pin "30") (pinfunction "30_30") (pintype "passive"))
      (node (ref "F40BOT") (pin "17") (pinfunction "1_17") (pintype "passive"))
      (node (ref "T79") (pin "2") (pinfunction "B_2") (pintype "passive"))
    )
    (net (code "270") (name "unconnected-(C40-Pad3)") (class "Default")
      (node (ref "C40") (pin "3") (pinfunction "3_3") (pintype "passive"))
    )
    (net (code "271") (name "unconnected-(C40-Pad4)") (class "Default")
      (node (ref "C40") (pin "4") (pinfunction "4_4") (pintype "passive"))
    )
    (net (code "272") (name "unconnected-(C40-Pad5)") (class "Default")
      (node (ref "C40") (pin "5") (pinfunction "5_5") (pintype "passive"))
    )
    (net (code "273") (name "unconnected-(C40-Pad6)") (class "Default")
      (node (ref "C40") (pin "6") (pinfunction "6_6") (pintype "passive"))
    )
    (net (code "274") (name "unconnected-(C40-Pad7)") (class "Default")
      (node (ref "C40") (pin "7") (pinfunction "7_7") (pintype "passive"))
    )
    (net (code "275") (name "unconnected-(C40-Pad8)") (class "Default")
      (node (ref "C40") (pin "8") (pinfunction "8_8") (pintype "passive"))
    )
    (net (code "276") (name "unconnected-(C40-Pad13)") (class "Default")
      (node (ref "C40") (pin "13") (pinfunction "13_13") (pintype "passive"))
    )
    (net (code "277") (name "unconnected-(C40-Pad14)") (class "Default")
      (node (ref "C40") (pin "14") (pinfunction "14_14") (pintype "passive"))
    )
    (net (code "278") (name "unconnected-(C40-Pad15)") (class "Default")
      (node (ref "C40") (pin "15") (pinfunction "15_15") (pintype "passive"))
    )
    (net (code "279") (name "unconnected-(C40-Pad16)") (class "Default")
      (node (ref "C40") (pin "16") (pinfunction "16_16") (pintype "passive"))
    )
    (net (code "280") (name "unconnected-(C40-Pad21)") (class "Default")
      (node (ref "C40") (pin "21") (pinfunction "21_21") (pintype "passive"))
    )
    (net (code "281") (name "unconnected-(C40-Pad22)") (class "Default")
      (node (ref "C40") (pin "22") (pinfunction "22_22") (pintype "passive"))
    )
    (net (code "282") (name "unconnected-(C40-Pad26)") (class "Default")
      (node (ref "C40") (pin "26") (pinfunction "26_26") (pintype "passive"))
    )
    (net (code "283") (name "unconnected-(C40-Pad27)") (class "Default")
      (node (ref "C40") (pin "27") (pinfunction "27_27") (pintype "passive"))
    )
    (net (code "284") (name "unconnected-(C40-Pad29)") (class "Default")
      (node (ref "C40") (pin "29") (pinfunction "29_29") (pintype "passive"))
    )
    (net (code "285") (name "unconnected-(C40-Pad30)") (class "Default")
      (node (ref "C40") (pin "30") (pinfunction "30_30") (pintype "passive"))
    )
    (net (code "286") (name "unconnected-(C40-Pad31)") (class "Default")
      (node (ref "C40") (pin "31") (pinfunction "31_31") (pintype "passive"))
    )
    (net (code "287") (name "unconnected-(C40-Pad32)") (class "Default")
      (node (ref "C40") (pin "32") (pinfunction "32_32") (pintype "passive"))
    )
    (net (code "288") (name "unconnected-(D40-Pad1)") (class "Default")
      (node (ref "D40") (pin "1") (pinfunction "1_1") (pintype "passive"))
    )
    (net (code "289") (name "unconnected-(D40-Pad3)") (class "Default")
      (node (ref "D40") (pin "3") (pinfunction "3_3") (pintype "passive"))
    )
    (net (code "290") (name "unconnected-(D40-Pad5)") (class "Default")
      (node (ref "D40") (pin "5") (pinfunction "5_5") (pintype "passive"))
    )
    (net (code "291") (name "unconnected-(D40-Pad7)") (class "Default")
      (node (ref "D40") (pin "7") (pinfunction "7_7") (pintype "passive"))
    )
    (net (code "292") (name "unconnected-(D40-Pad9)") (class "Default")
      (node (ref "D40") (pin "9") (pinfunction "9_9") (pintype "passive"))
    )
    (net (code "293") (name "unconnected-(D40-Pad11)") (class "Default")
      (node (ref "D40") (pin "11") (pinfunction "11_11") (pintype "passive"))
    )
    (net (code "294") (name "unconnected-(D40-Pad13)") (class "Default")
      (node (ref "D40") (pin "13") (pinfunction "13_13") (pintype "passive"))
    )
    (net (code "295") (name "unconnected-(D40-Pad14)") (class "Default")
      (node (ref "D40") (pin "14") (pinfunction "14_14") (pintype "passive"))
    )
    (net (code "296") (name "unconnected-(D40-Pad15)") (class "Default")
      (node (ref "D40") (pin "15") (pinfunction "15_15") (pintype "passive"))
    )
    (net (code "297") (name "unconnected-(D40-Pad21)") (class "Default")
      (node (ref "D40") (pin "21") (pinfunction "21_21") (pintype "passive"))
    )
    (net (code "298") (name "unconnected-(D40-Pad25)") (class "Default")
      (node (ref "D40") (pin "25") (pinfunction "25_25") (pintype "passive"))
    )
    (net (code "299") (name "unconnected-(D40-Pad27)") (class "Default")
      (node (ref "D40") (pin "27") (pinfunction "27_27") (pintype "passive"))
    )
    (net (code "300") (name "unconnected-(D40-Pad29)") (class "Default")
      (node (ref "D40") (pin "29") (pinfunction "29_29") (pintype "passive"))
    )
  )
)
